# cloudArray2.net
KiCad netlist of a schematic drawn in EAGLE
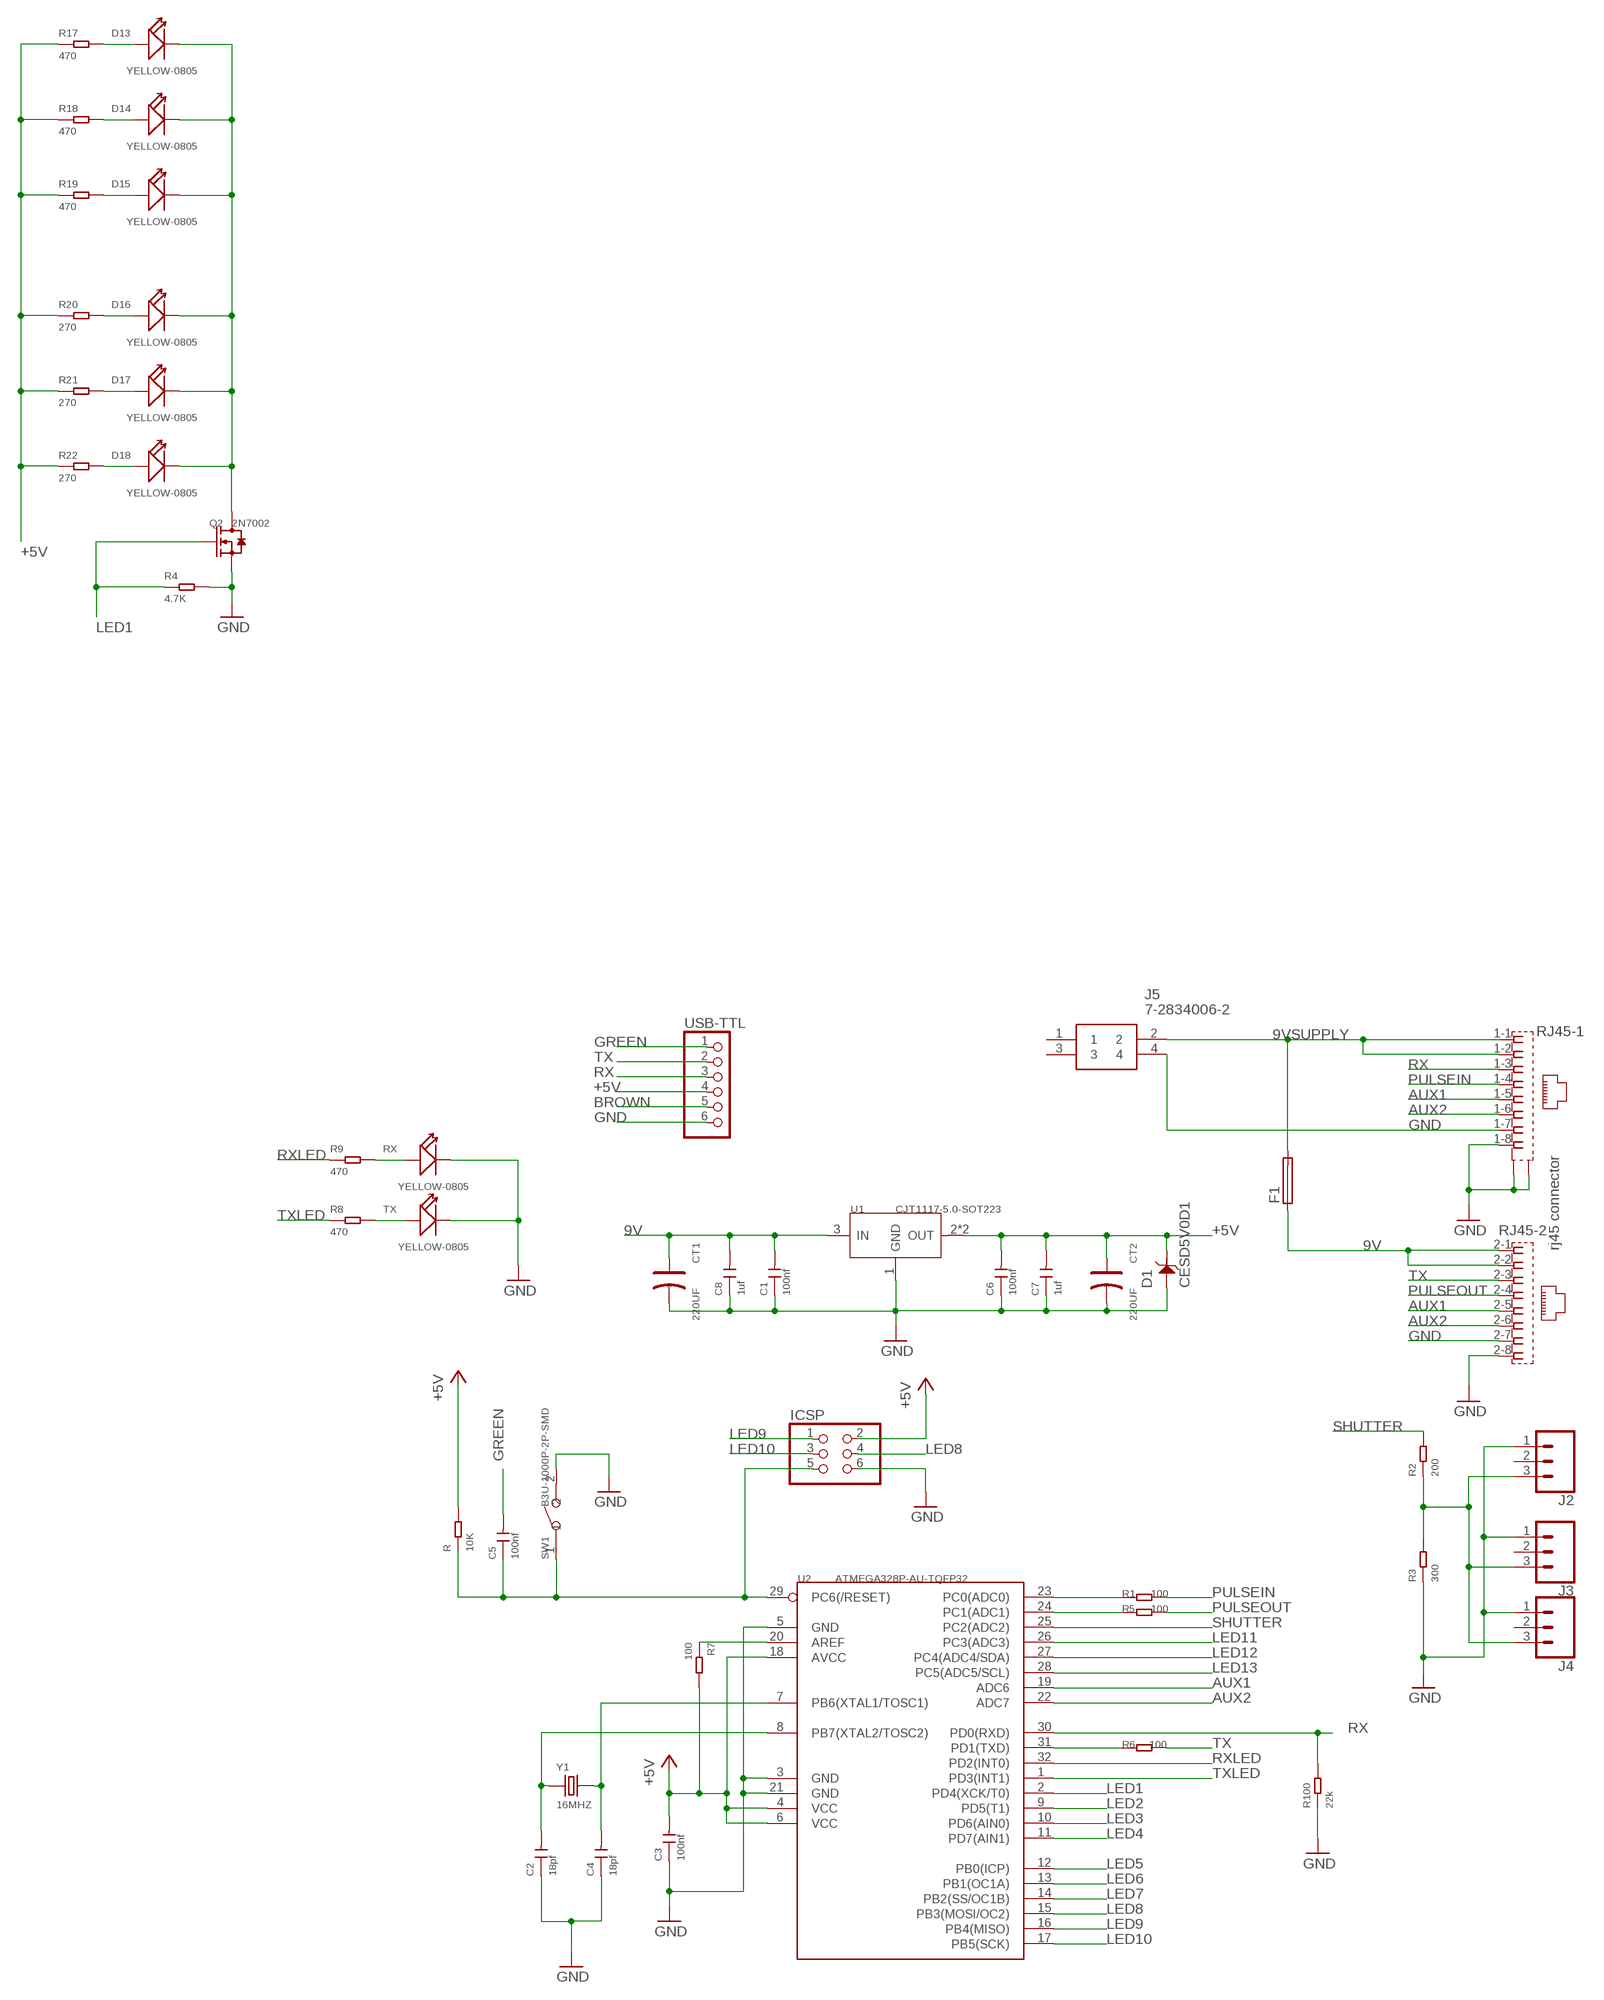
[diagram p0: schematic, sheet 1]
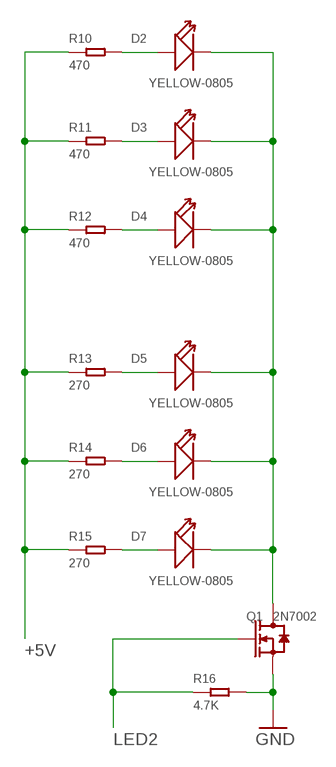
[diagram p1: schematic, sheet 2]
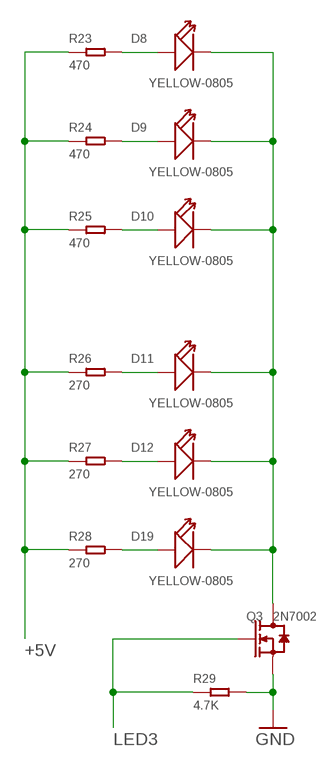
[diagram p2: schematic, sheet 3]
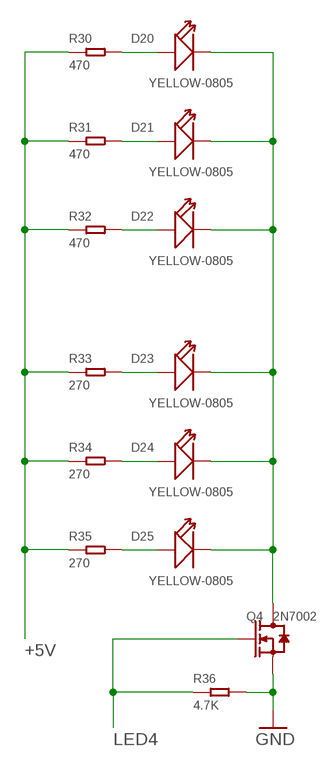
[diagram p3: schematic, sheet 4]
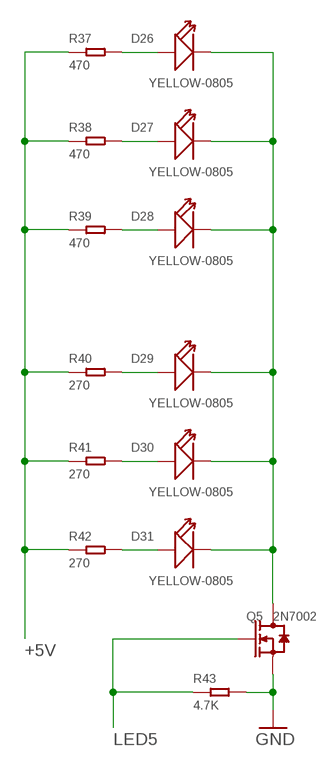
[diagram p4: schematic, sheet 5]
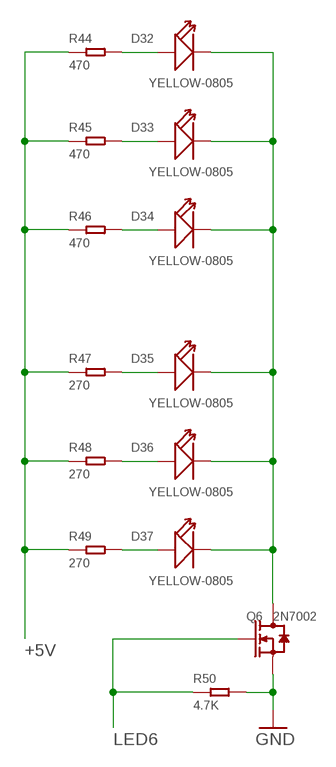
[diagram p5: schematic, sheet 6]
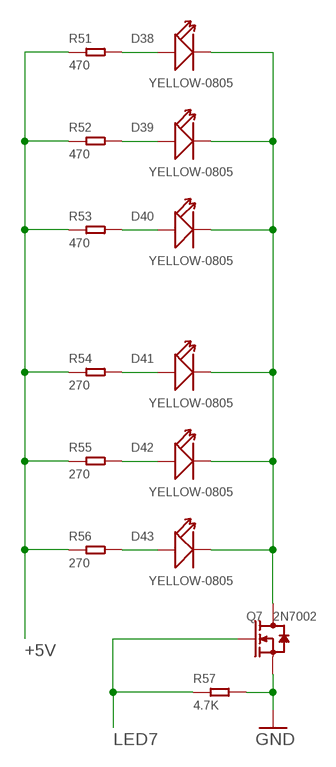
[diagram p6: schematic, sheet 7]
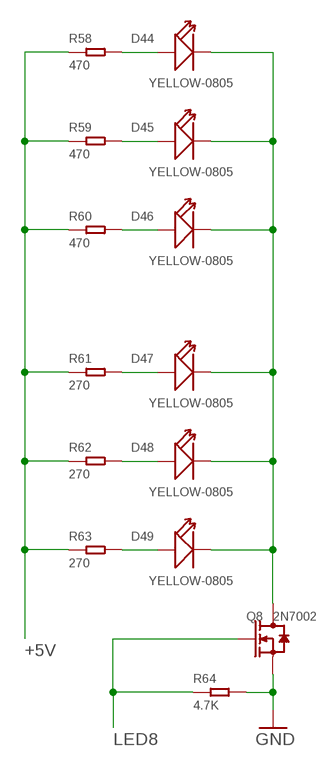
[diagram p7: schematic, sheet 8]
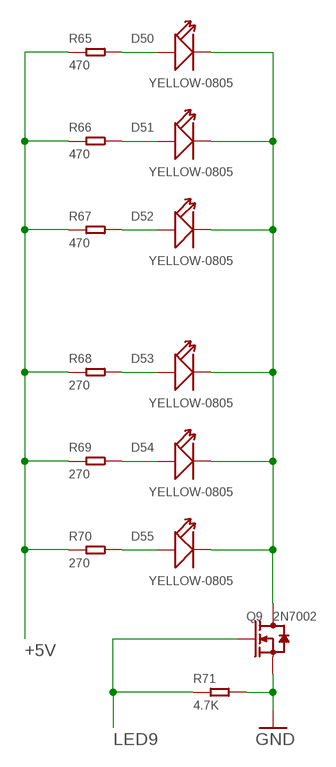
[diagram p8: schematic, sheet 9]
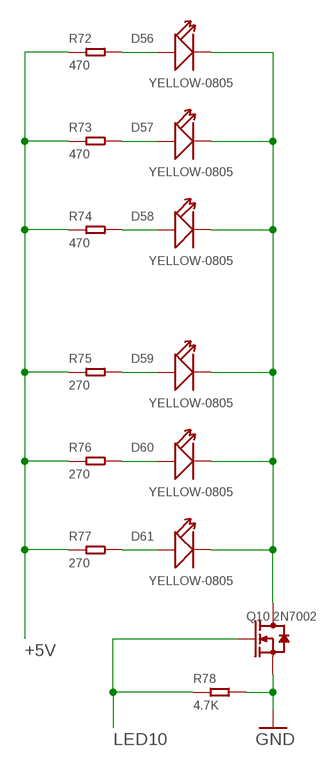
[diagram p9: schematic, sheet 10]
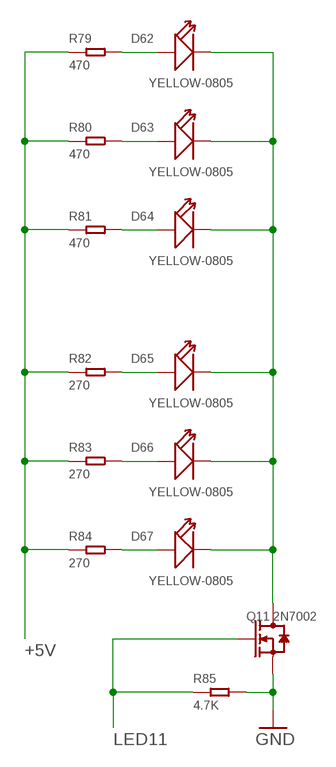
[diagram p10: schematic, sheet 11]
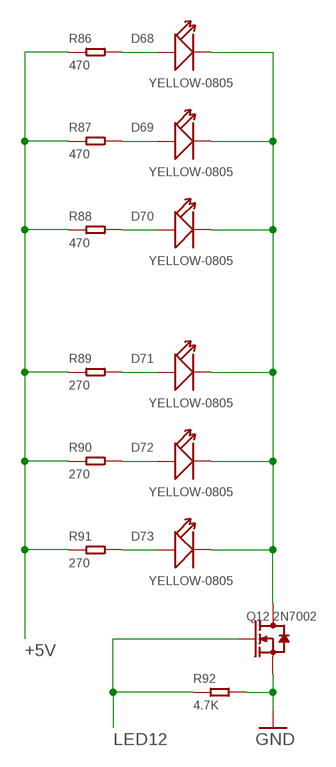
[diagram p11: schematic, sheet 12]
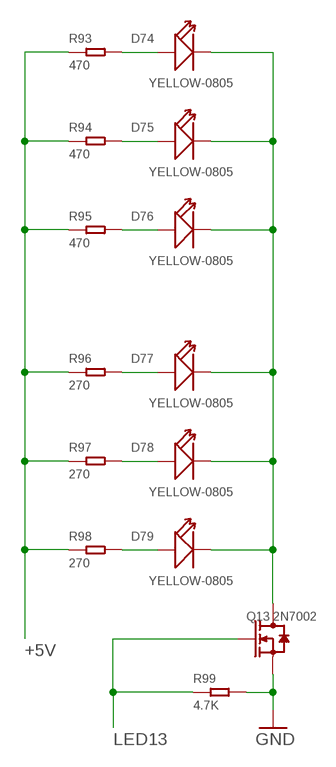
[diagram p12: schematic, sheet 13]

(export (version "E")
  (design (tool "Eeschema 10.0.6"))
  (components
    (comp (ref "D38")
      (value "YELLOW-0805")
      (footprint "eagle-import:LED-0805")
      (fields (field (name "MPN") "17-215UYC/S530-A3/TR8"))
      (libsource (lib "eagle-import") (part "SMD-LED-CLEAR-YELLOW(0805)"))
    )
    (comp (ref "D39")
      (value "YELLOW-0805")
      (footprint "eagle-import:LED-0805")
      (fields (field (name "MPN") "17-215UYC/S530-A3/TR8"))
      (libsource (lib "eagle-import") (part "SMD-LED-CLEAR-YELLOW(0805)"))
    )
    (comp (ref "D40")
      (value "YELLOW-0805")
      (footprint "eagle-import:LED-0805")
      (fields (field (name "MPN") "17-215UYC/S530-A3/TR8"))
      (libsource (lib "eagle-import") (part "SMD-LED-CLEAR-YELLOW(0805)"))
    )
    (comp (ref "D41")
      (value "YELLOW-0805")
      (footprint "eagle-import:LED-0805")
      (fields (field (name "MPN") "17-215UYC/S530-A3/TR8"))
      (libsource (lib "eagle-import") (part "SMD-LED-CLEAR-YELLOW(0805)"))
    )
    (comp (ref "D42")
      (value "YELLOW-0805")
      (footprint "eagle-import:LED-0805")
      (fields (field (name "MPN") "17-215UYC/S530-A3/TR8"))
      (libsource (lib "eagle-import") (part "SMD-LED-CLEAR-YELLOW(0805)"))
    )
    (comp (ref "D43")
      (value "YELLOW-0805")
      (footprint "eagle-import:LED-0805")
      (fields (field (name "MPN") "17-215UYC/S530-A3/TR8"))
      (libsource (lib "eagle-import") (part "SMD-LED-CLEAR-YELLOW(0805)"))
    )
    (comp (ref "Q7")
      (value "2N7002")
      (footprint "eagle-import:SOT-23")
      (fields (field (name "MPN") "2N7002,215"))
      (libsource (lib "eagle-import") (part "SMD-MOSFET-N-CH-60V-300MA-LOGIC-LEVEL-FET-2N7002(SOT-23)"))
    )
    (comp (ref "R51")
      (value "470")
      (footprint "eagle-import:R0805")
      (fields (field (name "MPN") "RC0805JR-071KL"))
      (libsource (lib "eagle-import") (part "SMD-RES-470R-1%-1/8W(0805)"))
    )
    (comp (ref "R52")
      (value "470")
      (footprint "eagle-import:R0805")
      (fields (field (name "MPN") "RC0805JR-071KL"))
      (libsource (lib "eagle-import") (part "SMD-RES-470R-1%-1/8W(0805)"))
    )
    (comp (ref "R53")
      (value "470")
      (footprint "eagle-import:R0805")
      (fields (field (name "MPN") "RC0805JR-071KL"))
      (libsource (lib "eagle-import") (part "SMD-RES-470R-1%-1/8W(0805)"))
    )
    (comp (ref "R54")
      (value "270")
      (footprint "eagle-import:R0805")
      (fields (field (name "MPN") "RC0805JR-071KL"))
      (libsource (lib "eagle-import") (part "SMD-RES-470R-1%-1/8W(0805)"))
    )
    (comp (ref "R55")
      (value "270")
      (footprint "eagle-import:R0805")
      (fields (field (name "MPN") "RC0805JR-071KL"))
      (libsource (lib "eagle-import") (part "SMD-RES-470R-1%-1/8W(0805)"))
    )
    (comp (ref "R56")
      (value "270")
      (footprint "eagle-import:R0805")
      (fields (field (name "MPN") "RC0805JR-071KL"))
      (libsource (lib "eagle-import") (part "SMD-RES-470R-1%-1/8W(0805)"))
    )
    (comp (ref "R57")
      (value "4.7K")
      (footprint "eagle-import:R0805")
      (fields (field (name "MPN") "RC0805JR-071KL"))
      (libsource (lib "eagle-import") (part "SMD-RES-2.4K-5%-1/8W(0805)"))
    )
    (comp (ref "D50")
      (value "YELLOW-0805")
      (footprint "eagle-import:LED-0805")
      (fields (field (name "MPN") "17-215UYC/S530-A3/TR8"))
      (libsource (lib "eagle-import") (part "SMD-LED-CLEAR-YELLOW(0805)"))
    )
    (comp (ref "D51")
      (value "YELLOW-0805")
      (footprint "eagle-import:LED-0805")
      (fields (field (name "MPN") "17-215UYC/S530-A3/TR8"))
      (libsource (lib "eagle-import") (part "SMD-LED-CLEAR-YELLOW(0805)"))
    )
    (comp (ref "D52")
      (value "YELLOW-0805")
      (footprint "eagle-import:LED-0805")
      (fields (field (name "MPN") "17-215UYC/S530-A3/TR8"))
      (libsource (lib "eagle-import") (part "SMD-LED-CLEAR-YELLOW(0805)"))
    )
    (comp (ref "D53")
      (value "YELLOW-0805")
      (footprint "eagle-import:LED-0805")
      (fields (field (name "MPN") "17-215UYC/S530-A3/TR8"))
      (libsource (lib "eagle-import") (part "SMD-LED-CLEAR-YELLOW(0805)"))
    )
    (comp (ref "D54")
      (value "YELLOW-0805")
      (footprint "eagle-import:LED-0805")
      (fields (field (name "MPN") "17-215UYC/S530-A3/TR8"))
      (libsource (lib "eagle-import") (part "SMD-LED-CLEAR-YELLOW(0805)"))
    )
    (comp (ref "D55")
      (value "YELLOW-0805")
      (footprint "eagle-import:LED-0805")
      (fields (field (name "MPN") "17-215UYC/S530-A3/TR8"))
      (libsource (lib "eagle-import") (part "SMD-LED-CLEAR-YELLOW(0805)"))
    )
    (comp (ref "Q9")
      (value "2N7002")
      (footprint "eagle-import:SOT-23")
      (fields (field (name "MPN") "2N7002,215"))
      (libsource (lib "eagle-import") (part "SMD-MOSFET-N-CH-60V-300MA-LOGIC-LEVEL-FET-2N7002(SOT-23)"))
    )
    (comp (ref "R65")
      (value "470")
      (footprint "eagle-import:R0805")
      (fields (field (name "MPN") "RC0805JR-071KL"))
      (libsource (lib "eagle-import") (part "SMD-RES-470R-1%-1/8W(0805)"))
    )
    (comp (ref "R66")
      (value "470")
      (footprint "eagle-import:R0805")
      (fields (field (name "MPN") "RC0805JR-071KL"))
      (libsource (lib "eagle-import") (part "SMD-RES-470R-1%-1/8W(0805)"))
    )
    (comp (ref "R67")
      (value "470")
      (footprint "eagle-import:R0805")
      (fields (field (name "MPN") "RC0805JR-071KL"))
      (libsource (lib "eagle-import") (part "SMD-RES-470R-1%-1/8W(0805)"))
    )
    (comp (ref "R68")
      (value "270")
      (footprint "eagle-import:R0805")
      (fields (field (name "MPN") "RC0805JR-071KL"))
      (libsource (lib "eagle-import") (part "SMD-RES-470R-1%-1/8W(0805)"))
    )
    (comp (ref "R69")
      (value "270")
      (footprint "eagle-import:R0805")
      (fields (field (name "MPN") "RC0805JR-071KL"))
      (libsource (lib "eagle-import") (part "SMD-RES-470R-1%-1/8W(0805)"))
    )
    (comp (ref "R70")
      (value "270")
      (footprint "eagle-import:R0805")
      (fields (field (name "MPN") "RC0805JR-071KL"))
      (libsource (lib "eagle-import") (part "SMD-RES-470R-1%-1/8W(0805)"))
    )
    (comp (ref "R71")
      (value "4.7K")
      (footprint "eagle-import:R0805")
      (fields (field (name "MPN") "RC0805JR-071KL"))
      (libsource (lib "eagle-import") (part "SMD-RES-2.4K-5%-1/8W(0805)"))
    )
    (comp (ref "D68")
      (value "YELLOW-0805")
      (footprint "eagle-import:LED-0805")
      (fields (field (name "MPN") "17-215UYC/S530-A3/TR8"))
      (libsource (lib "eagle-import") (part "SMD-LED-CLEAR-YELLOW(0805)"))
    )
    (comp (ref "D69")
      (value "YELLOW-0805")
      (footprint "eagle-import:LED-0805")
      (fields (field (name "MPN") "17-215UYC/S530-A3/TR8"))
      (libsource (lib "eagle-import") (part "SMD-LED-CLEAR-YELLOW(0805)"))
    )
    (comp (ref "D70")
      (value "YELLOW-0805")
      (footprint "eagle-import:LED-0805")
      (fields (field (name "MPN") "17-215UYC/S530-A3/TR8"))
      (libsource (lib "eagle-import") (part "SMD-LED-CLEAR-YELLOW(0805)"))
    )
    (comp (ref "D71")
      (value "YELLOW-0805")
      (footprint "eagle-import:LED-0805")
      (fields (field (name "MPN") "17-215UYC/S530-A3/TR8"))
      (libsource (lib "eagle-import") (part "SMD-LED-CLEAR-YELLOW(0805)"))
    )
    (comp (ref "D72")
      (value "YELLOW-0805")
      (footprint "eagle-import:LED-0805")
      (fields (field (name "MPN") "17-215UYC/S530-A3/TR8"))
      (libsource (lib "eagle-import") (part "SMD-LED-CLEAR-YELLOW(0805)"))
    )
    (comp (ref "D73")
      (value "YELLOW-0805")
      (footprint "eagle-import:LED-0805")
      (fields (field (name "MPN") "17-215UYC/S530-A3/TR8"))
      (libsource (lib "eagle-import") (part "SMD-LED-CLEAR-YELLOW(0805)"))
    )
    (comp (ref "Q12")
      (value "2N7002")
      (footprint "eagle-import:SOT-23")
      (fields (field (name "MPN") "2N7002,215"))
      (libsource (lib "eagle-import") (part "SMD-MOSFET-N-CH-60V-300MA-LOGIC-LEVEL-FET-2N7002(SOT-23)"))
    )
    (comp (ref "R86")
      (value "470")
      (footprint "eagle-import:R0805")
      (fields (field (name "MPN") "RC0805JR-071KL"))
      (libsource (lib "eagle-import") (part "SMD-RES-470R-1%-1/8W(0805)"))
    )
    (comp (ref "R87")
      (value "470")
      (footprint "eagle-import:R0805")
      (fields (field (name "MPN") "RC0805JR-071KL"))
      (libsource (lib "eagle-import") (part "SMD-RES-470R-1%-1/8W(0805)"))
    )
    (comp (ref "R88")
      (value "470")
      (footprint "eagle-import:R0805")
      (fields (field (name "MPN") "RC0805JR-071KL"))
      (libsource (lib "eagle-import") (part "SMD-RES-470R-1%-1/8W(0805)"))
    )
    (comp (ref "R89")
      (value "270")
      (footprint "eagle-import:R0805")
      (fields (field (name "MPN") "RC0805JR-071KL"))
      (libsource (lib "eagle-import") (part "SMD-RES-470R-1%-1/8W(0805)"))
    )
    (comp (ref "R90")
      (value "270")
      (footprint "eagle-import:R0805")
      (fields (field (name "MPN") "RC0805JR-071KL"))
      (libsource (lib "eagle-import") (part "SMD-RES-470R-1%-1/8W(0805)"))
    )
    (comp (ref "R91")
      (value "270")
      (footprint "eagle-import:R0805")
      (fields (field (name "MPN") "RC0805JR-071KL"))
      (libsource (lib "eagle-import") (part "SMD-RES-470R-1%-1/8W(0805)"))
    )
    (comp (ref "R92")
      (value "4.7K")
      (footprint "eagle-import:R0805")
      (fields (field (name "MPN") "RC0805JR-071KL"))
      (libsource (lib "eagle-import") (part "SMD-RES-2.4K-5%-1/8W(0805)"))
    )
    (comp (ref "D26")
      (value "YELLOW-0805")
      (footprint "eagle-import:LED-0805")
      (fields (field (name "MPN") "17-215UYC/S530-A3/TR8"))
      (libsource (lib "eagle-import") (part "SMD-LED-CLEAR-YELLOW(0805)"))
    )
    (comp (ref "D27")
      (value "YELLOW-0805")
      (footprint "eagle-import:LED-0805")
      (fields (field (name "MPN") "17-215UYC/S530-A3/TR8"))
      (libsource (lib "eagle-import") (part "SMD-LED-CLEAR-YELLOW(0805)"))
    )
    (comp (ref "D28")
      (value "YELLOW-0805")
      (footprint "eagle-import:LED-0805")
      (fields (field (name "MPN") "17-215UYC/S530-A3/TR8"))
      (libsource (lib "eagle-import") (part "SMD-LED-CLEAR-YELLOW(0805)"))
    )
    (comp (ref "D29")
      (value "YELLOW-0805")
      (footprint "eagle-import:LED-0805")
      (fields (field (name "MPN") "17-215UYC/S530-A3/TR8"))
      (libsource (lib "eagle-import") (part "SMD-LED-CLEAR-YELLOW(0805)"))
    )
    (comp (ref "D30")
      (value "YELLOW-0805")
      (footprint "eagle-import:LED-0805")
      (fields (field (name "MPN") "17-215UYC/S530-A3/TR8"))
      (libsource (lib "eagle-import") (part "SMD-LED-CLEAR-YELLOW(0805)"))
    )
    (comp (ref "D31")
      (value "YELLOW-0805")
      (footprint "eagle-import:LED-0805")
      (fields (field (name "MPN") "17-215UYC/S530-A3/TR8"))
      (libsource (lib "eagle-import") (part "SMD-LED-CLEAR-YELLOW(0805)"))
    )
    (comp (ref "Q5")
      (value "2N7002")
      (footprint "eagle-import:SOT-23")
      (fields (field (name "MPN") "2N7002,215"))
      (libsource (lib "eagle-import") (part "SMD-MOSFET-N-CH-60V-300MA-LOGIC-LEVEL-FET-2N7002(SOT-23)"))
    )
    (comp (ref "R37")
      (value "470")
      (footprint "eagle-import:R0805")
      (fields (field (name "MPN") "RC0805JR-071KL"))
      (libsource (lib "eagle-import") (part "SMD-RES-470R-1%-1/8W(0805)"))
    )
    (comp (ref "R38")
      (value "470")
      (footprint "eagle-import:R0805")
      (fields (field (name "MPN") "RC0805JR-071KL"))
      (libsource (lib "eagle-import") (part "SMD-RES-470R-1%-1/8W(0805)"))
    )
    (comp (ref "R39")
      (value "470")
      (footprint "eagle-import:R0805")
      (fields (field (name "MPN") "RC0805JR-071KL"))
      (libsource (lib "eagle-import") (part "SMD-RES-470R-1%-1/8W(0805)"))
    )
    (comp (ref "R40")
      (value "270")
      (footprint "eagle-import:R0805")
      (fields (field (name "MPN") "RC0805JR-071KL"))
      (libsource (lib "eagle-import") (part "SMD-RES-470R-1%-1/8W(0805)"))
    )
    (comp (ref "R41")
      (value "270")
      (footprint "eagle-import:R0805")
      (fields (field (name "MPN") "RC0805JR-071KL"))
      (libsource (lib "eagle-import") (part "SMD-RES-470R-1%-1/8W(0805)"))
    )
    (comp (ref "R42")
      (value "270")
      (footprint "eagle-import:R0805")
      (fields (field (name "MPN") "RC0805JR-071KL"))
      (libsource (lib "eagle-import") (part "SMD-RES-470R-1%-1/8W(0805)"))
    )
    (comp (ref "R43")
      (value "4.7K")
      (footprint "eagle-import:R0805")
      (fields (field (name "MPN") "RC0805JR-071KL"))
      (libsource (lib "eagle-import") (part "SMD-RES-2.4K-5%-1/8W(0805)"))
    )
    (comp (ref "D74")
      (value "YELLOW-0805")
      (footprint "eagle-import:LED-0805")
      (fields (field (name "MPN") "17-215UYC/S530-A3/TR8"))
      (libsource (lib "eagle-import") (part "SMD-LED-CLEAR-YELLOW(0805)"))
    )
    (comp (ref "D75")
      (value "YELLOW-0805")
      (footprint "eagle-import:LED-0805")
      (fields (field (name "MPN") "17-215UYC/S530-A3/TR8"))
      (libsource (lib "eagle-import") (part "SMD-LED-CLEAR-YELLOW(0805)"))
    )
    (comp (ref "D76")
      (value "YELLOW-0805")
      (footprint "eagle-import:LED-0805")
      (fields (field (name "MPN") "17-215UYC/S530-A3/TR8"))
      (libsource (lib "eagle-import") (part "SMD-LED-CLEAR-YELLOW(0805)"))
    )
    (comp (ref "D77")
      (value "YELLOW-0805")
      (footprint "eagle-import:LED-0805")
      (fields (field (name "MPN") "17-215UYC/S530-A3/TR8"))
      (libsource (lib "eagle-import") (part "SMD-LED-CLEAR-YELLOW(0805)"))
    )
    (comp (ref "D78")
      (value "YELLOW-0805")
      (footprint "eagle-import:LED-0805")
      (fields (field (name "MPN") "17-215UYC/S530-A3/TR8"))
      (libsource (lib "eagle-import") (part "SMD-LED-CLEAR-YELLOW(0805)"))
    )
    (comp (ref "D79")
      (value "YELLOW-0805")
      (footprint "eagle-import:LED-0805")
      (fields (field (name "MPN") "17-215UYC/S530-A3/TR8"))
      (libsource (lib "eagle-import") (part "SMD-LED-CLEAR-YELLOW(0805)"))
    )
    (comp (ref "Q13")
      (value "2N7002")
      (footprint "eagle-import:SOT-23")
      (fields (field (name "MPN") "2N7002,215"))
      (libsource (lib "eagle-import") (part "SMD-MOSFET-N-CH-60V-300MA-LOGIC-LEVEL-FET-2N7002(SOT-23)"))
    )
    (comp (ref "R93")
      (value "470")
      (footprint "eagle-import:R0805")
      (fields (field (name "MPN") "RC0805JR-071KL"))
      (libsource (lib "eagle-import") (part "SMD-RES-470R-1%-1/8W(0805)"))
    )
    (comp (ref "R94")
      (value "470")
      (footprint "eagle-import:R0805")
      (fields (field (name "MPN") "RC0805JR-071KL"))
      (libsource (lib "eagle-import") (part "SMD-RES-470R-1%-1/8W(0805)"))
    )
    (comp (ref "R95")
      (value "470")
      (footprint "eagle-import:R0805")
      (fields (field (name "MPN") "RC0805JR-071KL"))
      (libsource (lib "eagle-import") (part "SMD-RES-470R-1%-1/8W(0805)"))
    )
    (comp (ref "R96")
      (value "270")
      (footprint "eagle-import:R0805")
      (fields (field (name "MPN") "RC0805JR-071KL"))
      (libsource (lib "eagle-import") (part "SMD-RES-470R-1%-1/8W(0805)"))
    )
    (comp (ref "R97")
      (value "270")
      (footprint "eagle-import:R0805")
      (fields (field (name "MPN") "RC0805JR-071KL"))
      (libsource (lib "eagle-import") (part "SMD-RES-470R-1%-1/8W(0805)"))
    )
    (comp (ref "R98")
      (value "270")
      (footprint "eagle-import:R0805")
      (fields (field (name "MPN") "RC0805JR-071KL"))
      (libsource (lib "eagle-import") (part "SMD-RES-470R-1%-1/8W(0805)"))
    )
    (comp (ref "R99")
      (value "4.7K")
      (footprint "eagle-import:R0805")
      (fields (field (name "MPN") "RC0805JR-071KL"))
      (libsource (lib "eagle-import") (part "SMD-RES-2.4K-5%-1/8W(0805)"))
    )
    (comp (ref "D20")
      (value "YELLOW-0805")
      (footprint "eagle-import:LED-0805")
      (fields (field (name "MPN") "17-215UYC/S530-A3/TR8"))
      (libsource (lib "eagle-import") (part "SMD-LED-CLEAR-YELLOW(0805)"))
    )
    (comp (ref "D21")
      (value "YELLOW-0805")
      (footprint "eagle-import:LED-0805")
      (fields (field (name "MPN") "17-215UYC/S530-A3/TR8"))
      (libsource (lib "eagle-import") (part "SMD-LED-CLEAR-YELLOW(0805)"))
    )
    (comp (ref "D22")
      (value "YELLOW-0805")
      (footprint "eagle-import:LED-0805")
      (fields (field (name "MPN") "17-215UYC/S530-A3/TR8"))
      (libsource (lib "eagle-import") (part "SMD-LED-CLEAR-YELLOW(0805)"))
    )
    (comp (ref "D23")
      (value "YELLOW-0805")
      (footprint "eagle-import:LED-0805")
      (fields (field (name "MPN") "17-215UYC/S530-A3/TR8"))
      (libsource (lib "eagle-import") (part "SMD-LED-CLEAR-YELLOW(0805)"))
    )
    (comp (ref "D24")
      (value "YELLOW-0805")
      (footprint "eagle-import:LED-0805")
      (fields (field (name "MPN") "17-215UYC/S530-A3/TR8"))
      (libsource (lib "eagle-import") (part "SMD-LED-CLEAR-YELLOW(0805)"))
    )
    (comp (ref "D25")
      (value "YELLOW-0805")
      (footprint "eagle-import:LED-0805")
      (fields (field (name "MPN") "17-215UYC/S530-A3/TR8"))
      (libsource (lib "eagle-import") (part "SMD-LED-CLEAR-YELLOW(0805)"))
    )
    (comp (ref "Q4")
      (value "2N7002")
      (footprint "eagle-import:SOT-23")
      (fields (field (name "MPN") "2N7002,215"))
      (libsource (lib "eagle-import") (part "SMD-MOSFET-N-CH-60V-300MA-LOGIC-LEVEL-FET-2N7002(SOT-23)"))
    )
    (comp (ref "R30")
      (value "470")
      (footprint "eagle-import:R0805")
      (fields (field (name "MPN") "RC0805JR-071KL"))
      (libsource (lib "eagle-import") (part "SMD-RES-470R-1%-1/8W(0805)"))
    )
    (comp (ref "R31")
      (value "470")
      (footprint "eagle-import:R0805")
      (fields (field (name "MPN") "RC0805JR-071KL"))
      (libsource (lib "eagle-import") (part "SMD-RES-470R-1%-1/8W(0805)"))
    )
    (comp (ref "R32")
      (value "470")
      (footprint "eagle-import:R0805")
      (fields (field (name "MPN") "RC0805JR-071KL"))
      (libsource (lib "eagle-import") (part "SMD-RES-470R-1%-1/8W(0805)"))
    )
    (comp (ref "R33")
      (value "270")
      (footprint "eagle-import:R0805")
      (fields (field (name "MPN") "RC0805JR-071KL"))
      (libsource (lib "eagle-import") (part "SMD-RES-470R-1%-1/8W(0805)"))
    )
    (comp (ref "R34")
      (value "270")
      (footprint "eagle-import:R0805")
      (fields (field (name "MPN") "RC0805JR-071KL"))
      (libsource (lib "eagle-import") (part "SMD-RES-470R-1%-1/8W(0805)"))
    )
    (comp (ref "R35")
      (value "270")
      (footprint "eagle-import:R0805")
      (fields (field (name "MPN") "RC0805JR-071KL"))
      (libsource (lib "eagle-import") (part "SMD-RES-470R-1%-1/8W(0805)"))
    )
    (comp (ref "R36")
      (value "4.7K")
      (footprint "eagle-import:R0805")
      (fields (field (name "MPN") "RC0805JR-071KL"))
      (libsource (lib "eagle-import") (part "SMD-RES-2.4K-5%-1/8W(0805)"))
    )
    (comp (ref "D44")
      (value "YELLOW-0805")
      (footprint "eagle-import:LED-0805")
      (fields (field (name "MPN") "17-215UYC/S530-A3/TR8"))
      (libsource (lib "eagle-import") (part "SMD-LED-CLEAR-YELLOW(0805)"))
    )
    (comp (ref "D45")
      (value "YELLOW-0805")
      (footprint "eagle-import:LED-0805")
      (fields (field (name "MPN") "17-215UYC/S530-A3/TR8"))
      (libsource (lib "eagle-import") (part "SMD-LED-CLEAR-YELLOW(0805)"))
    )
    (comp (ref "D46")
      (value "YELLOW-0805")
      (footprint "eagle-import:LED-0805")
      (fields (field (name "MPN") "17-215UYC/S530-A3/TR8"))
      (libsource (lib "eagle-import") (part "SMD-LED-CLEAR-YELLOW(0805)"))
    )
    (comp (ref "D47")
      (value "YELLOW-0805")
      (footprint "eagle-import:LED-0805")
      (fields (field (name "MPN") "17-215UYC/S530-A3/TR8"))
      (libsource (lib "eagle-import") (part "SMD-LED-CLEAR-YELLOW(0805)"))
    )
    (comp (ref "D48")
      (value "YELLOW-0805")
      (footprint "eagle-import:LED-0805")
      (fields (field (name "MPN") "17-215UYC/S530-A3/TR8"))
      (libsource (lib "eagle-import") (part "SMD-LED-CLEAR-YELLOW(0805)"))
    )
    (comp (ref "D49")
      (value "YELLOW-0805")
      (footprint "eagle-import:LED-0805")
      (fields (field (name "MPN") "17-215UYC/S530-A3/TR8"))
      (libsource (lib "eagle-import") (part "SMD-LED-CLEAR-YELLOW(0805)"))
    )
    (comp (ref "Q8")
      (value "2N7002")
      (footprint "eagle-import:SOT-23")
      (fields (field (name "MPN") "2N7002,215"))
      (libsource (lib "eagle-import") (part "SMD-MOSFET-N-CH-60V-300MA-LOGIC-LEVEL-FET-2N7002(SOT-23)"))
    )
    (comp (ref "R58")
      (value "470")
      (footprint "eagle-import:R0805")
      (fields (field (name "MPN") "RC0805JR-071KL"))
      (libsource (lib "eagle-import") (part "SMD-RES-470R-1%-1/8W(0805)"))
    )
    (comp (ref "R59")
      (value "470")
      (footprint "eagle-import:R0805")
      (fields (field (name "MPN") "RC0805JR-071KL"))
      (libsource (lib "eagle-import") (part "SMD-RES-470R-1%-1/8W(0805)"))
    )
    (comp (ref "R60")
      (value "470")
      (footprint "eagle-import:R0805")
      (fields (field (name "MPN") "RC0805JR-071KL"))
      (libsource (lib "eagle-import") (part "SMD-RES-470R-1%-1/8W(0805)"))
    )
    (comp (ref "R61")
      (value "270")
      (footprint "eagle-import:R0805")
      (fields (field (name "MPN") "RC0805JR-071KL"))
      (libsource (lib "eagle-import") (part "SMD-RES-470R-1%-1/8W(0805)"))
    )
    (comp (ref "R62")
      (value "270")
      (footprint "eagle-import:R0805")
      (fields (field (name "MPN") "RC0805JR-071KL"))
      (libsource (lib "eagle-import") (part "SMD-RES-470R-1%-1/8W(0805)"))
    )
    (comp (ref "R63")
      (value "270")
      (footprint "eagle-import:R0805")
      (fields (field (name "MPN") "RC0805JR-071KL"))
      (libsource (lib "eagle-import") (part "SMD-RES-470R-1%-1/8W(0805)"))
    )
    (comp (ref "R64")
      (value "4.7K")
      (footprint "eagle-import:R0805")
      (fields (field (name "MPN") "RC0805JR-071KL"))
      (libsource (lib "eagle-import") (part "SMD-RES-2.4K-5%-1/8W(0805)"))
    )
    (comp (ref "C1")
      (value "100nf")
      (footprint "eagle-import:C0805")
      (fields (field (name "MPN") "CC0805KRX7R9BB104"))
      (libsource (lib "eagle-import") (part "CERAMIC-100NF-50V-10%-X7R(0805)"))
    )
    (comp (ref "C2")
      (value "18pf")
      (footprint "eagle-import:C0805")
      (fields (field (name "MPN") "CC0805KKX7R8BB105"))
      (libsource (lib "eagle-import") (part "CERAMIC-1UF-25V-10%-X7R(0805)"))
    )
    (comp (ref "C3")
      (value "100nf")
      (footprint "eagle-import:C0805")
      (fields (field (name "MPN") "CC0805JRX7R9BB103"))
      (libsource (lib "eagle-import") (part "CERAMIC-10NF-50V-5%-X7R(0805)"))
    )
    (comp (ref "C4")
      (value "18pf")
      (footprint "eagle-import:C0805")
      (fields (field (name "MPN") "CC0805KKX7R8BB105"))
      (libsource (lib "eagle-import") (part "CERAMIC-1UF-25V-10%-X7R(0805)"))
    )
    (comp (ref "C5")
      (value "100nf")
      (footprint "eagle-import:C0805")
      (fields (field (name "MPN") "CC0805KRX7R9BB104"))
      (libsource (lib "eagle-import") (part "CERAMIC-100NF-50V-10%-X7R(0805)"))
    )
    (comp (ref "C6")
      (value "100nf")
      (footprint "eagle-import:C0805")
      (fields (field (name "MPN") "CC0805KRX7R9BB104"))
      (libsource (lib "eagle-import") (part "CERAMIC-100NF-50V-10%-X7R(0805)"))
    )
    (comp (ref "C7")
      (value "1uf")
      (footprint "eagle-import:C0805")
      (fields (field (name "MPN") "CC0805KRX7R9BB104"))
      (libsource (lib "eagle-import") (part "CERAMIC-100NF-50V-10%-X7R(0805)"))
    )
    (comp (ref "C8")
      (value "1uf")
      (footprint "eagle-import:C0805")
      (fields (field (name "MPN") "CC0805KRX7R9BB104"))
      (libsource (lib "eagle-import") (part "CERAMIC-100NF-50V-10%-X7R(0805)"))
    )
    (comp (ref "CT1")
      (value "220UF")
      (footprint "eagle-import:ELECTRO-SMD-C-6MM")
      (fields (field (name "MPN") "CS1E221M-CRE77"))
      (libsource (lib "eagle-import") (part "ALUMINUM-SMD-220UF-16V(D6.3-H7.7MM)"))
    )
    (comp (ref "CT2")
      (value "220UF")
      (footprint "eagle-import:ELECTRO-SMD-C-6MM")
      (fields (field (name "MPN") "CS1E221M-CRE77"))
      (libsource (lib "eagle-import") (part "ALUMINUM-SMD-220UF-16V(D6.3-H7.7MM)"))
    )
    (comp (ref "D1")
      (value "CESD5V0D1")
      (footprint "eagle-import:SOD-123")
      (libsource (lib "eagle-import") (part "SMD-DIODE-ESD-6.2V-250MW(SOD-123)"))
    )
    (comp (ref "D13")
      (value "YELLOW-0805")
      (footprint "eagle-import:LED-0805")
      (fields (field (name "MPN") "17-215UYC/S530-A3/TR8"))
      (libsource (lib "eagle-import") (part "SMD-LED-CLEAR-YELLOW(0805)"))
    )
    (comp (ref "D14")
      (value "YELLOW-0805")
      (footprint "eagle-import:LED-0805")
      (fields (field (name "MPN") "17-215UYC/S530-A3/TR8"))
      (libsource (lib "eagle-import") (part "SMD-LED-CLEAR-YELLOW(0805)"))
    )
    (comp (ref "D15")
      (value "YELLOW-0805")
      (footprint "eagle-import:LED-0805")
      (fields (field (name "MPN") "17-215UYC/S530-A3/TR8"))
      (libsource (lib "eagle-import") (part "SMD-LED-CLEAR-YELLOW(0805)"))
    )
    (comp (ref "D16")
      (value "YELLOW-0805")
      (footprint "eagle-import:LED-0805")
      (fields (field (name "MPN") "17-215UYC/S530-A3/TR8"))
      (libsource (lib "eagle-import") (part "SMD-LED-CLEAR-YELLOW(0805)"))
    )
    (comp (ref "D17")
      (value "YELLOW-0805")
      (footprint "eagle-import:LED-0805")
      (fields (field (name "MPN") "17-215UYC/S530-A3/TR8"))
      (libsource (lib "eagle-import") (part "SMD-LED-CLEAR-YELLOW(0805)"))
    )
    (comp (ref "D18")
      (value "YELLOW-0805")
      (footprint "eagle-import:LED-0805")
      (fields (field (name "MPN") "17-215UYC/S530-A3/TR8"))
      (libsource (lib "eagle-import") (part "SMD-LED-CLEAR-YELLOW(0805)"))
    )
    (comp (ref "F1")
      (value "SH22,5A")
      (footprint "eagle-import:SH22,5A")
      (fields (field (name "MPN") "0031.7701.11"))
      (libsource (lib "eagle-import") (part "SH22,5A"))
    )
    (comp (ref "ICSP")
      (value "PINHD-2X3")
      (footprint "eagle-import:2X03")
      (libsource (lib "eagle-import") (part "PINHD-2X3"))
    )
    (comp (ref "J2")
      (value "455-1750-1-ND")
      (footprint "eagle-import:1X03")
      (libsource (lib "eagle-import") (part "CONN_03"))
    )
    (comp (ref "J3")
      (value "455-1750-1-ND")
      (footprint "eagle-import:1X03")
      (libsource (lib "eagle-import") (part "CONN_03"))
    )
    (comp (ref "J4")
      (value "455-1750-1-ND")
      (footprint "eagle-import:1X03")
      (libsource (lib "eagle-import") (part "CONN_03"))
    )
    (comp (ref "J5")
      (value "7-2834006-2")
      (footprint "eagle-import:728340062")
      (fields (field (name "MOUSER_PART_NUMBER") "571-7-2834006-2"))
      (libsource (lib "eagle-import") (part "7-2834006-2"))
    )
    (comp (ref "Q2")
      (value "2N7002")
      (footprint "eagle-import:SOT-23")
      (fields (field (name "MPN") "2N7002,215"))
      (libsource (lib "eagle-import") (part "SMD-MOSFET-N-CH-60V-300MA-LOGIC-LEVEL-FET-2N7002(SOT-23)"))
    )
    (comp (ref "R")
      (value "10K")
      (footprint "eagle-import:R0805")
      (fields (field (name "MPN") "RC0805FR-0710KL"))
      (libsource (lib "eagle-import") (part "SMD-RES-10K-1%-1/8W(0805)"))
    )
    (comp (ref "R1")
      (value "100")
      (footprint "eagle-import:R0805")
      (fields (field (name "MPN") "RC0805JR-071KL"))
      (libsource (lib "eagle-import") (part "SMD-RES-200R-1%-1/8W(0805)"))
    )
    (comp (ref "R2")
      (value "200")
      (footprint "eagle-import:R0805")
      (fields (field (name "MPN") "RC0805JR-071KL"))
      (libsource (lib "eagle-import") (part "SMD-RES-200R-1%-1/8W(0805)"))
    )
    (comp (ref "R3")
      (value "300")
      (footprint "eagle-import:R0805")
      (fields (field (name "MPN") "RC0805JR-071KL"))
      (libsource (lib "eagle-import") (part "SMD-RES-200R-1%-1/8W(0805)"))
    )
    (comp (ref "R4")
      (value "4.7K")
      (footprint "eagle-import:R0805")
      (fields (field (name "MPN") "RC0805JR-071KL"))
      (libsource (lib "eagle-import") (part "SMD-RES-2.4K-5%-1/8W(0805)"))
    )
    (comp (ref "R5")
      (value "100")
      (footprint "eagle-import:R0805")
      (fields (field (name "MPN") "RC0805JR-071KL"))
      (libsource (lib "eagle-import") (part "SMD-RES-200R-1%-1/8W(0805)"))
    )
    (comp (ref "R6")
      (value "100")
      (footprint "eagle-import:R0805")
      (fields (field (name "MPN") "RC0805JR-071KL"))
      (libsource (lib "eagle-import") (part "SMD-RES-200R-1%-1/8W(0805)"))
    )
    (comp (ref "R7")
      (value "100")
      (footprint "eagle-import:R0805")
      (fields (field (name "MPN") "RC0805JR-071KL"))
      (libsource (lib "eagle-import") (part "SMD-RES-200R-1%-1/8W(0805)"))
    )
    (comp (ref "R8")
      (value "470")
      (footprint "eagle-import:R0805")
      (fields (field (name "MPN") "RC0805JR-071KL"))
      (libsource (lib "eagle-import") (part "SMD-RES-470R-1%-1/8W(0805)"))
    )
    (comp (ref "R9")
      (value "470")
      (footprint "eagle-import:R0805")
      (fields (field (name "MPN") "RC0805JR-071KL"))
      (libsource (lib "eagle-import") (part "SMD-RES-470R-1%-1/8W(0805)"))
    )
    (comp (ref "R17")
      (value "470")
      (footprint "eagle-import:R0805")
      (fields (field (name "MPN") "RC0805JR-071KL"))
      (libsource (lib "eagle-import") (part "SMD-RES-470R-1%-1/8W(0805)"))
    )
    (comp (ref "R18")
      (value "470")
      (footprint "eagle-import:R0805")
      (fields (field (name "MPN") "RC0805JR-071KL"))
      (libsource (lib "eagle-import") (part "SMD-RES-470R-1%-1/8W(0805)"))
    )
    (comp (ref "R19")
      (value "470")
      (footprint "eagle-import:R0805")
      (fields (field (name "MPN") "RC0805JR-071KL"))
      (libsource (lib "eagle-import") (part "SMD-RES-470R-1%-1/8W(0805)"))
    )
    (comp (ref "R20")
      (value "270")
      (footprint "eagle-import:R0805")
      (fields (field (name "MPN") "RC0805JR-071KL"))
      (libsource (lib "eagle-import") (part "SMD-RES-470R-1%-1/8W(0805)"))
    )
    (comp (ref "R21")
      (value "270")
      (footprint "eagle-import:R0805")
      (fields (field (name "MPN") "RC0805JR-071KL"))
      (libsource (lib "eagle-import") (part "SMD-RES-470R-1%-1/8W(0805)"))
    )
    (comp (ref "R22")
      (value "270")
      (footprint "eagle-import:R0805")
      (fields (field (name "MPN") "RC0805JR-071KL"))
      (libsource (lib "eagle-import") (part "SMD-RES-470R-1%-1/8W(0805)"))
    )
    (comp (ref "R100")
      (value "22k")
      (footprint "eagle-import:R0805")
      (fields (field (name "MPN") "RC0805JR-071KL"))
      (libsource (lib "eagle-import") (part "SMD-RES-200R-1%-1/8W(0805)"))
    )
    (comp (ref "RJ45")
      (value "557570-1")
      (footprint "eagle-import:557570-1")
      (libsource (lib "eagle-import") (part "557570-1"))
    )
    (comp (ref "RX")
      (value "YELLOW-0805")
      (footprint "eagle-import:LED-0805")
      (fields (field (name "MPN") "17-215UYC/S530-A3/TR8"))
      (libsource (lib "eagle-import") (part "SMD-LED-CLEAR-YELLOW(0805)"))
    )
    (comp (ref "SW1")
      (value "B3U-1000P-2P-SMD")
      (footprint "eagle-import:SW2-2.6-3.0X2.5X1.2+0.4MM")
      (libsource (lib "eagle-import") (part "SMD-BUTTON(2P-3.0X2.5X1.2+0.4MM)-B3U-1000P-2P-SMD"))
    )
    (comp (ref "TX")
      (value "YELLOW-0805")
      (footprint "eagle-import:LED-0805")
      (fields (field (name "MPN") "17-215UYC/S530-A3/TR8"))
      (libsource (lib "eagle-import") (part "SMD-LED-CLEAR-YELLOW(0805)"))
    )
    (comp (ref "U1")
      (value "CJT1117-5.0-SOT223")
      (footprint "eagle-import:SOT-223")
      (fields (field (name "MPN") "CJT1117-5.0"))
      (libsource (lib "eagle-import") (part "PMIC-CJT1117-5.0(SOT223)"))
    )
    (comp (ref "U2")
      (value "ATMEGA328P-AU-TQFP32")
      (footprint "eagle-import:TQFP32-0.8-7X7MM")
      (fields (field (name "MPN") "ATMEGA328P-AU"))
      (libsource (lib "eagle-import") (part "MCU-ATMEGA328P-AU(TQFP32)"))
    )
    (comp (ref "USB-TTL")
      (value "PINHD-1X6")
      (footprint "eagle-import:1X06")
      (libsource (lib "eagle-import") (part "PINHD-1X6"))
    )
    (comp (ref "Y1")
      (value "16MHZ")
      (footprint "eagle-import:X2-SMD-5.0X3.2X1.3MM")
      (fields (field (name "MPN") "X053201602002"))
      (libsource (lib "eagle-import") (part "SMD-CRYSTAL-16MHZ-8PF-20PPM-40R(2P-5.0X3.2MM)"))
    )
    (comp (ref "D8")
      (value "YELLOW-0805")
      (footprint "eagle-import:LED-0805")
      (fields (field (name "MPN") "17-215UYC/S530-A3/TR8"))
      (libsource (lib "eagle-import") (part "SMD-LED-CLEAR-YELLOW(0805)"))
    )
    (comp (ref "D9")
      (value "YELLOW-0805")
      (footprint "eagle-import:LED-0805")
      (fields (field (name "MPN") "17-215UYC/S530-A3/TR8"))
      (libsource (lib "eagle-import") (part "SMD-LED-CLEAR-YELLOW(0805)"))
    )
    (comp (ref "D10")
      (value "YELLOW-0805")
      (footprint "eagle-import:LED-0805")
      (fields (field (name "MPN") "17-215UYC/S530-A3/TR8"))
      (libsource (lib "eagle-import") (part "SMD-LED-CLEAR-YELLOW(0805)"))
    )
    (comp (ref "D11")
      (value "YELLOW-0805")
      (footprint "eagle-import:LED-0805")
      (fields (field (name "MPN") "17-215UYC/S530-A3/TR8"))
      (libsource (lib "eagle-import") (part "SMD-LED-CLEAR-YELLOW(0805)"))
    )
    (comp (ref "D12")
      (value "YELLOW-0805")
      (footprint "eagle-import:LED-0805")
      (fields (field (name "MPN") "17-215UYC/S530-A3/TR8"))
      (libsource (lib "eagle-import") (part "SMD-LED-CLEAR-YELLOW(0805)"))
    )
    (comp (ref "D19")
      (value "YELLOW-0805")
      (footprint "eagle-import:LED-0805")
      (fields (field (name "MPN") "17-215UYC/S530-A3/TR8"))
      (libsource (lib "eagle-import") (part "SMD-LED-CLEAR-YELLOW(0805)"))
    )
    (comp (ref "Q3")
      (value "2N7002")
      (footprint "eagle-import:SOT-23")
      (fields (field (name "MPN") "2N7002,215"))
      (libsource (lib "eagle-import") (part "SMD-MOSFET-N-CH-60V-300MA-LOGIC-LEVEL-FET-2N7002(SOT-23)"))
    )
    (comp (ref "R23")
      (value "470")
      (footprint "eagle-import:R0805")
      (fields (field (name "MPN") "RC0805JR-071KL"))
      (libsource (lib "eagle-import") (part "SMD-RES-470R-1%-1/8W(0805)"))
    )
    (comp (ref "R24")
      (value "470")
      (footprint "eagle-import:R0805")
      (fields (field (name "MPN") "RC0805JR-071KL"))
      (libsource (lib "eagle-import") (part "SMD-RES-470R-1%-1/8W(0805)"))
    )
    (comp (ref "R25")
      (value "470")
      (footprint "eagle-import:R0805")
      (fields (field (name "MPN") "RC0805JR-071KL"))
      (libsource (lib "eagle-import") (part "SMD-RES-470R-1%-1/8W(0805)"))
    )
    (comp (ref "R26")
      (value "270")
      (footprint "eagle-import:R0805")
      (fields (field (name "MPN") "RC0805JR-071KL"))
      (libsource (lib "eagle-import") (part "SMD-RES-470R-1%-1/8W(0805)"))
    )
    (comp (ref "R27")
      (value "270")
      (footprint "eagle-import:R0805")
      (fields (field (name "MPN") "RC0805JR-071KL"))
      (libsource (lib "eagle-import") (part "SMD-RES-470R-1%-1/8W(0805)"))
    )
    (comp (ref "R28")
      (value "270")
      (footprint "eagle-import:R0805")
      (fields (field (name "MPN") "RC0805JR-071KL"))
      (libsource (lib "eagle-import") (part "SMD-RES-470R-1%-1/8W(0805)"))
    )
    (comp (ref "R29")
      (value "4.7K")
      (footprint "eagle-import:R0805")
      (fields (field (name "MPN") "RC0805JR-071KL"))
      (libsource (lib "eagle-import") (part "SMD-RES-2.4K-5%-1/8W(0805)"))
    )
    (comp (ref "D32")
      (value "YELLOW-0805")
      (footprint "eagle-import:LED-0805")
      (fields (field (name "MPN") "17-215UYC/S530-A3/TR8"))
      (libsource (lib "eagle-import") (part "SMD-LED-CLEAR-YELLOW(0805)"))
    )
    (comp (ref "D33")
      (value "YELLOW-0805")
      (footprint "eagle-import:LED-0805")
      (fields (field (name "MPN") "17-215UYC/S530-A3/TR8"))
      (libsource (lib "eagle-import") (part "SMD-LED-CLEAR-YELLOW(0805)"))
    )
    (comp (ref "D34")
      (value "YELLOW-0805")
      (footprint "eagle-import:LED-0805")
      (fields (field (name "MPN") "17-215UYC/S530-A3/TR8"))
      (libsource (lib "eagle-import") (part "SMD-LED-CLEAR-YELLOW(0805)"))
    )
    (comp (ref "D35")
      (value "YELLOW-0805")
      (footprint "eagle-import:LED-0805")
      (fields (field (name "MPN") "17-215UYC/S530-A3/TR8"))
      (libsource (lib "eagle-import") (part "SMD-LED-CLEAR-YELLOW(0805)"))
    )
    (comp (ref "D36")
      (value "YELLOW-0805")
      (footprint "eagle-import:LED-0805")
      (fields (field (name "MPN") "17-215UYC/S530-A3/TR8"))
      (libsource (lib "eagle-import") (part "SMD-LED-CLEAR-YELLOW(0805)"))
    )
    (comp (ref "D37")
      (value "YELLOW-0805")
      (footprint "eagle-import:LED-0805")
      (fields (field (name "MPN") "17-215UYC/S530-A3/TR8"))
      (libsource (lib "eagle-import") (part "SMD-LED-CLEAR-YELLOW(0805)"))
    )
    (comp (ref "Q6")
      (value "2N7002")
      (footprint "eagle-import:SOT-23")
      (fields (field (name "MPN") "2N7002,215"))
      (libsource (lib "eagle-import") (part "SMD-MOSFET-N-CH-60V-300MA-LOGIC-LEVEL-FET-2N7002(SOT-23)"))
    )
    (comp (ref "R44")
      (value "470")
      (footprint "eagle-import:R0805")
      (fields (field (name "MPN") "RC0805JR-071KL"))
      (libsource (lib "eagle-import") (part "SMD-RES-470R-1%-1/8W(0805)"))
    )
    (comp (ref "R45")
      (value "470")
      (footprint "eagle-import:R0805")
      (fields (field (name "MPN") "RC0805JR-071KL"))
      (libsource (lib "eagle-import") (part "SMD-RES-470R-1%-1/8W(0805)"))
    )
    (comp (ref "R46")
      (value "470")
      (footprint "eagle-import:R0805")
      (fields (field (name "MPN") "RC0805JR-071KL"))
      (libsource (lib "eagle-import") (part "SMD-RES-470R-1%-1/8W(0805)"))
    )
    (comp (ref "R47")
      (value "270")
      (footprint "eagle-import:R0805")
      (fields (field (name "MPN") "RC0805JR-071KL"))
      (libsource (lib "eagle-import") (part "SMD-RES-470R-1%-1/8W(0805)"))
    )
    (comp (ref "R48")
      (value "270")
      (footprint "eagle-import:R0805")
      (fields (field (name "MPN") "RC0805JR-071KL"))
      (libsource (lib "eagle-import") (part "SMD-RES-470R-1%-1/8W(0805)"))
    )
    (comp (ref "R49")
      (value "270")
      (footprint "eagle-import:R0805")
      (fields (field (name "MPN") "RC0805JR-071KL"))
      (libsource (lib "eagle-import") (part "SMD-RES-470R-1%-1/8W(0805)"))
    )
    (comp (ref "R50")
      (value "4.7K")
      (footprint "eagle-import:R0805")
      (fields (field (name "MPN") "RC0805JR-071KL"))
      (libsource (lib "eagle-import") (part "SMD-RES-2.4K-5%-1/8W(0805)"))
    )
    (comp (ref "D62")
      (value "YELLOW-0805")
      (footprint "eagle-import:LED-0805")
      (fields (field (name "MPN") "17-215UYC/S530-A3/TR8"))
      (libsource (lib "eagle-import") (part "SMD-LED-CLEAR-YELLOW(0805)"))
    )
    (comp (ref "D63")
      (value "YELLOW-0805")
      (footprint "eagle-import:LED-0805")
      (fields (field (name "MPN") "17-215UYC/S530-A3/TR8"))
      (libsource (lib "eagle-import") (part "SMD-LED-CLEAR-YELLOW(0805)"))
    )
    (comp (ref "D64")
      (value "YELLOW-0805")
      (footprint "eagle-import:LED-0805")
      (fields (field (name "MPN") "17-215UYC/S530-A3/TR8"))
      (libsource (lib "eagle-import") (part "SMD-LED-CLEAR-YELLOW(0805)"))
    )
    (comp (ref "D65")
      (value "YELLOW-0805")
      (footprint "eagle-import:LED-0805")
      (fields (field (name "MPN") "17-215UYC/S530-A3/TR8"))
      (libsource (lib "eagle-import") (part "SMD-LED-CLEAR-YELLOW(0805)"))
    )
    (comp (ref "D66")
      (value "YELLOW-0805")
      (footprint "eagle-import:LED-0805")
      (fields (field (name "MPN") "17-215UYC/S530-A3/TR8"))
      (libsource (lib "eagle-import") (part "SMD-LED-CLEAR-YELLOW(0805)"))
    )
    (comp (ref "D67")
      (value "YELLOW-0805")
      (footprint "eagle-import:LED-0805")
      (fields (field (name "MPN") "17-215UYC/S530-A3/TR8"))
      (libsource (lib "eagle-import") (part "SMD-LED-CLEAR-YELLOW(0805)"))
    )
    (comp (ref "Q11")
      (value "2N7002")
      (footprint "eagle-import:SOT-23")
      (fields (field (name "MPN") "2N7002,215"))
      (libsource (lib "eagle-import") (part "SMD-MOSFET-N-CH-60V-300MA-LOGIC-LEVEL-FET-2N7002(SOT-23)"))
    )
    (comp (ref "R79")
      (value "470")
      (footprint "eagle-import:R0805")
      (fields (field (name "MPN") "RC0805JR-071KL"))
      (libsource (lib "eagle-import") (part "SMD-RES-470R-1%-1/8W(0805)"))
    )
    (comp (ref "R80")
      (value "470")
      (footprint "eagle-import:R0805")
      (fields (field (name "MPN") "RC0805JR-071KL"))
      (libsource (lib "eagle-import") (part "SMD-RES-470R-1%-1/8W(0805)"))
    )
    (comp (ref "R81")
      (value "470")
      (footprint "eagle-import:R0805")
      (fields (field (name "MPN") "RC0805JR-071KL"))
      (libsource (lib "eagle-import") (part "SMD-RES-470R-1%-1/8W(0805)"))
    )
    (comp (ref "R82")
      (value "270")
      (footprint "eagle-import:R0805")
      (fields (field (name "MPN") "RC0805JR-071KL"))
      (libsource (lib "eagle-import") (part "SMD-RES-470R-1%-1/8W(0805)"))
    )
    (comp (ref "R83")
      (value "270")
      (footprint "eagle-import:R0805")
      (fields (field (name "MPN") "RC0805JR-071KL"))
      (libsource (lib "eagle-import") (part "SMD-RES-470R-1%-1/8W(0805)"))
    )
    (comp (ref "R84")
      (value "270")
      (footprint "eagle-import:R0805")
      (fields (field (name "MPN") "RC0805JR-071KL"))
      (libsource (lib "eagle-import") (part "SMD-RES-470R-1%-1/8W(0805)"))
    )
    (comp (ref "R85")
      (value "4.7K")
      (footprint "eagle-import:R0805")
      (fields (field (name "MPN") "RC0805JR-071KL"))
      (libsource (lib "eagle-import") (part "SMD-RES-2.4K-5%-1/8W(0805)"))
    )
    (comp (ref "D56")
      (value "YELLOW-0805")
      (footprint "eagle-import:LED-0805")
      (fields (field (name "MPN") "17-215UYC/S530-A3/TR8"))
      (libsource (lib "eagle-import") (part "SMD-LED-CLEAR-YELLOW(0805)"))
    )
    (comp (ref "D57")
      (value "YELLOW-0805")
      (footprint "eagle-import:LED-0805")
      (fields (field (name "MPN") "17-215UYC/S530-A3/TR8"))
      (libsource (lib "eagle-import") (part "SMD-LED-CLEAR-YELLOW(0805)"))
    )
    (comp (ref "D58")
      (value "YELLOW-0805")
      (footprint "eagle-import:LED-0805")
      (fields (field (name "MPN") "17-215UYC/S530-A3/TR8"))
      (libsource (lib "eagle-import") (part "SMD-LED-CLEAR-YELLOW(0805)"))
    )
    (comp (ref "D59")
      (value "YELLOW-0805")
      (footprint "eagle-import:LED-0805")
      (fields (field (name "MPN") "17-215UYC/S530-A3/TR8"))
      (libsource (lib "eagle-import") (part "SMD-LED-CLEAR-YELLOW(0805)"))
    )
    (comp (ref "D60")
      (value "YELLOW-0805")
      (footprint "eagle-import:LED-0805")
      (fields (field (name "MPN") "17-215UYC/S530-A3/TR8"))
      (libsource (lib "eagle-import") (part "SMD-LED-CLEAR-YELLOW(0805)"))
    )
    (comp (ref "D61")
      (value "YELLOW-0805")
      (footprint "eagle-import:LED-0805")
      (fields (field (name "MPN") "17-215UYC/S530-A3/TR8"))
      (libsource (lib "eagle-import") (part "SMD-LED-CLEAR-YELLOW(0805)"))
    )
    (comp (ref "Q10")
      (value "2N7002")
      (footprint "eagle-import:SOT-23")
      (fields (field (name "MPN") "2N7002,215"))
      (libsource (lib "eagle-import") (part "SMD-MOSFET-N-CH-60V-300MA-LOGIC-LEVEL-FET-2N7002(SOT-23)"))
    )
    (comp (ref "R72")
      (value "470")
      (footprint "eagle-import:R0805")
      (fields (field (name "MPN") "RC0805JR-071KL"))
      (libsource (lib "eagle-import") (part "SMD-RES-470R-1%-1/8W(0805)"))
    )
    (comp (ref "R73")
      (value "470")
      (footprint "eagle-import:R0805")
      (fields (field (name "MPN") "RC0805JR-071KL"))
      (libsource (lib "eagle-import") (part "SMD-RES-470R-1%-1/8W(0805)"))
    )
    (comp (ref "R74")
      (value "470")
      (footprint "eagle-import:R0805")
      (fields (field (name "MPN") "RC0805JR-071KL"))
      (libsource (lib "eagle-import") (part "SMD-RES-470R-1%-1/8W(0805)"))
    )
    (comp (ref "R75")
      (value "270")
      (footprint "eagle-import:R0805")
      (fields (field (name "MPN") "RC0805JR-071KL"))
      (libsource (lib "eagle-import") (part "SMD-RES-470R-1%-1/8W(0805)"))
    )
    (comp (ref "R76")
      (value "270")
      (footprint "eagle-import:R0805")
      (fields (field (name "MPN") "RC0805JR-071KL"))
      (libsource (lib "eagle-import") (part "SMD-RES-470R-1%-1/8W(0805)"))
    )
    (comp (ref "R77")
      (value "270")
      (footprint "eagle-import:R0805")
      (fields (field (name "MPN") "RC0805JR-071KL"))
      (libsource (lib "eagle-import") (part "SMD-RES-470R-1%-1/8W(0805)"))
    )
    (comp (ref "R78")
      (value "4.7K")
      (footprint "eagle-import:R0805")
      (fields (field (name "MPN") "RC0805JR-071KL"))
      (libsource (lib "eagle-import") (part "SMD-RES-2.4K-5%-1/8W(0805)"))
    )
    (comp (ref "D2")
      (value "YELLOW-0805")
      (footprint "eagle-import:LED-0805")
      (fields (field (name "MPN") "17-215UYC/S530-A3/TR8"))
      (libsource (lib "eagle-import") (part "SMD-LED-CLEAR-YELLOW(0805)"))
    )
    (comp (ref "D3")
      (value "YELLOW-0805")
      (footprint "eagle-import:LED-0805")
      (fields (field (name "MPN") "17-215UYC/S530-A3/TR8"))
      (libsource (lib "eagle-import") (part "SMD-LED-CLEAR-YELLOW(0805)"))
    )
    (comp (ref "D4")
      (value "YELLOW-0805")
      (footprint "eagle-import:LED-0805")
      (fields (field (name "MPN") "17-215UYC/S530-A3/TR8"))
      (libsource (lib "eagle-import") (part "SMD-LED-CLEAR-YELLOW(0805)"))
    )
    (comp (ref "D5")
      (value "YELLOW-0805")
      (footprint "eagle-import:LED-0805")
      (fields (field (name "MPN") "17-215UYC/S530-A3/TR8"))
      (libsource (lib "eagle-import") (part "SMD-LED-CLEAR-YELLOW(0805)"))
    )
    (comp (ref "D6")
      (value "YELLOW-0805")
      (footprint "eagle-import:LED-0805")
      (fields (field (name "MPN") "17-215UYC/S530-A3/TR8"))
      (libsource (lib "eagle-import") (part "SMD-LED-CLEAR-YELLOW(0805)"))
    )
    (comp (ref "D7")
      (value "YELLOW-0805")
      (footprint "eagle-import:LED-0805")
      (fields (field (name "MPN") "17-215UYC/S530-A3/TR8"))
      (libsource (lib "eagle-import") (part "SMD-LED-CLEAR-YELLOW(0805)"))
    )
    (comp (ref "Q1")
      (value "2N7002")
      (footprint "eagle-import:SOT-23")
      (fields (field (name "MPN") "2N7002,215"))
      (libsource (lib "eagle-import") (part "SMD-MOSFET-N-CH-60V-300MA-LOGIC-LEVEL-FET-2N7002(SOT-23)"))
    )
    (comp (ref "R10")
      (value "470")
      (footprint "eagle-import:R0805")
      (fields (field (name "MPN") "RC0805JR-071KL"))
      (libsource (lib "eagle-import") (part "SMD-RES-470R-1%-1/8W(0805)"))
    )
    (comp (ref "R11")
      (value "470")
      (footprint "eagle-import:R0805")
      (fields (field (name "MPN") "RC0805JR-071KL"))
      (libsource (lib "eagle-import") (part "SMD-RES-470R-1%-1/8W(0805)"))
    )
    (comp (ref "R12")
      (value "470")
      (footprint "eagle-import:R0805")
      (fields (field (name "MPN") "RC0805JR-071KL"))
      (libsource (lib "eagle-import") (part "SMD-RES-470R-1%-1/8W(0805)"))
    )
    (comp (ref "R13")
      (value "270")
      (footprint "eagle-import:R0805")
      (fields (field (name "MPN") "RC0805JR-071KL"))
      (libsource (lib "eagle-import") (part "SMD-RES-470R-1%-1/8W(0805)"))
    )
    (comp (ref "R14")
      (value "270")
      (footprint "eagle-import:R0805")
      (fields (field (name "MPN") "RC0805JR-071KL"))
      (libsource (lib "eagle-import") (part "SMD-RES-470R-1%-1/8W(0805)"))
    )
    (comp (ref "R15")
      (value "270")
      (footprint "eagle-import:R0805")
      (fields (field (name "MPN") "RC0805JR-071KL"))
      (libsource (lib "eagle-import") (part "SMD-RES-470R-1%-1/8W(0805)"))
    )
    (comp (ref "R16")
      (value "4.7K")
      (footprint "eagle-import:R0805")
      (fields (field (name "MPN") "RC0805JR-071KL"))
      (libsource (lib "eagle-import") (part "SMD-RES-2.4K-5%-1/8W(0805)"))
    )
  )
  (nets
    (net (code "1") (name "+5V") (class "Default")
      (node (ref "C3") (pin "2") (pinfunction "2_2") (pintype "passive"))
      (node (ref "C6") (pin "2") (pinfunction "2_2") (pintype "passive"))
      (node (ref "C7") (pin "2") (pinfunction "2_2") (pintype "passive"))
      (node (ref "CT2") (pin "+") (pinfunction "+_+") (pintype "passive"))
      (node (ref "D1") (pin "-") (pinfunction "2_-") (pintype "bidirectional"))
      (node (ref "ICSP") (pin "2") (pinfunction "2_2") (pintype "passive"))
      (node (ref "R") (pin "2") (pinfunction "2_2") (pintype "passive"))
      (node (ref "R10") (pin "1") (pinfunction "1_1") (pintype "passive"))
      (node (ref "R11") (pin "1") (pinfunction "1_1") (pintype "passive"))
      (node (ref "R12") (pin "1") (pinfunction "1_1") (pintype "passive"))
      (node (ref "R13") (pin "1") (pinfunction "1_1") (pintype "passive"))
      (node (ref "R14") (pin "1") (pinfunction "1_1") (pintype "passive"))
      (node (ref "R15") (pin "1") (pinfunction "1_1") (pintype "passive"))
      (node (ref "R17") (pin "1") (pinfunction "1_1") (pintype "passive"))
      (node (ref "R18") (pin "1") (pinfunction "1_1") (pintype "passive"))
      (node (ref "R19") (pin "1") (pinfunction "1_1") (pintype "passive"))
      (node (ref "R20") (pin "1") (pinfunction "1_1") (pintype "passive"))
      (node (ref "R21") (pin "1") (pinfunction "1_1") (pintype "passive"))
      (node (ref "R22") (pin "1") (pinfunction "1_1") (pintype "passive"))
      (node (ref "R23") (pin "1") (pinfunction "1_1") (pintype "passive"))
      (node (ref "R24") (pin "1") (pinfunction "1_1") (pintype "passive"))
      (node (ref "R25") (pin "1") (pinfunction "1_1") (pintype "passive"))
      (node (ref "R26") (pin "1") (pinfunction "1_1") (pintype "passive"))
      (node (ref "R27") (pin "1") (pinfunction "1_1") (pintype "passive"))
      (node (ref "R28") (pin "1") (pinfunction "1_1") (pintype "passive"))
      (node (ref "R30") (pin "1") (pinfunction "1_1") (pintype "passive"))
      (node (ref "R31") (pin "1") (pinfunction "1_1") (pintype "passive"))
      (node (ref "R32") (pin "1") (pinfunction "1_1") (pintype "passive"))
      (node (ref "R33") (pin "1") (pinfunction "1_1") (pintype "passive"))
      (node (ref "R34") (pin "1") (pinfunction "1_1") (pintype "passive"))
      (node (ref "R35") (pin "1") (pinfunction "1_1") (pintype "passive"))
      (node (ref "R37") (pin "1") (pinfunction "1_1") (pintype "passive"))
      (node (ref "R38") (pin "1") (pinfunction "1_1") (pintype "passive"))
      (node (ref "R39") (pin "1") (pinfunction "1_1") (pintype "passive"))
      (node (ref "R40") (pin "1") (pinfunction "1_1") (pintype "passive"))
      (node (ref "R41") (pin "1") (pinfunction "1_1") (pintype "passive"))
      (node (ref "R42") (pin "1") (pinfunction "1_1") (pintype "passive"))
      (node (ref "R44") (pin "1") (pinfunction "1_1") (pintype "passive"))
      (node (ref "R45") (pin "1") (pinfunction "1_1") (pintype "passive"))
      (node (ref "R46") (pin "1") (pinfunction "1_1") (pintype "passive"))
      (node (ref "R47") (pin "1") (pinfunction "1_1") (pintype "passive"))
      (node (ref "R48") (pin "1") (pinfunction "1_1") (pintype "passive"))
      (node (ref "R49") (pin "1") (pinfunction "1_1") (pintype "passive"))
      (node (ref "R51") (pin "1") (pinfunction "1_1") (pintype "passive"))
      (node (ref "R52") (pin "1") (pinfunction "1_1") (pintype "passive"))
      (node (ref "R53") (pin "1") (pinfunction "1_1") (pintype "passive"))
      (node (ref "R54") (pin "1") (pinfunction "1_1") (pintype "passive"))
      (node (ref "R55") (pin "1") (pinfunction "1_1") (pintype "passive"))
      (node (ref "R56") (pin "1") (pinfunction "1_1") (pintype "passive"))
      (node (ref "R58") (pin "1") (pinfunction "1_1") (pintype "passive"))
      (node (ref "R59") (pin "1") (pinfunction "1_1") (pintype "passive"))
      (node (ref "R60") (pin "1") (pinfunction "1_1") (pintype "passive"))
      (node (ref "R61") (pin "1") (pinfunction "1_1") (pintype "passive"))
      (node (ref "R62") (pin "1") (pinfunction "1_1") (pintype "passive"))
      (node (ref "R63") (pin "1") (pinfunction "1_1") (pintype "passive"))
      (node (ref "R65") (pin "1") (pinfunction "1_1") (pintype "passive"))
      (node (ref "R66") (pin "1") (pinfunction "1_1") (pintype "passive"))
      (node (ref "R67") (pin "1") (pinfunction "1_1") (pintype "passive"))
      (node (ref "R68") (pin "1") (pinfunction "1_1") (pintype "passive"))
      (node (ref "R69") (pin "1") (pinfunction "1_1") (pintype "passive"))
      (node (ref "R7") (pin "2") (pinfunction "2_2") (pintype "passive"))
      (node (ref "R70") (pin "1") (pinfunction "1_1") (pintype "passive"))
      (node (ref "R72") (pin "1") (pinfunction "1_1") (pintype "passive"))
      (node (ref "R73") (pin "1") (pinfunction "1_1") (pintype "passive"))
      (node (ref "R74") (pin "1") (pinfunction "1_1") (pintype "passive"))
      (node (ref "R75") (pin "1") (pinfunction "1_1") (pintype "passive"))
      (node (ref "R76") (pin "1") (pinfunction "1_1") (pintype "passive"))
      (node (ref "R77") (pin "1") (pinfunction "1_1") (pintype "passive"))
      (node (ref "R79") (pin "1") (pinfunction "1_1") (pintype "passive"))
      (node (ref "R80") (pin "1") (pinfunction "1_1") (pintype "passive"))
      (node (ref "R81") (pin "1") (pinfunction "1_1") (pintype "passive"))
      (node (ref "R82") (pin "1") (pinfunction "1_1") (pintype "passive"))
      (node (ref "R83") (pin "1") (pinfunction "1_1") (pintype "passive"))
      (node (ref "R84") (pin "1") (pinfunction "1_1") (pintype "passive"))
      (node (ref "R86") (pin "1") (pinfunction "1_1") (pintype "passive"))
      (node (ref "R87") (pin "1") (pinfunction "1_1") (pintype "passive"))
      (node (ref "R88") (pin "1") (pinfunction "1_1") (pintype "passive"))
      (node (ref "R89") (pin "1") (pinfunction "1_1") (pintype "passive"))
      (node (ref "R90") (pin "1") (pinfunction "1_1") (pintype "passive"))
      (node (ref "R91") (pin "1") (pinfunction "1_1") (pintype "passive"))
      (node (ref "R93") (pin "1") (pinfunction "1_1") (pintype "passive"))
      (node (ref "R94") (pin "1") (pinfunction "1_1") (pintype "passive"))
      (node (ref "R95") (pin "1") (pinfunction "1_1") (pintype "passive"))
      (node (ref "R96") (pin "1") (pinfunction "1_1") (pintype "passive"))
      (node (ref "R97") (pin "1") (pinfunction "1_1") (pintype "passive"))
      (node (ref "R98") (pin "1") (pinfunction "1_1") (pintype "passive"))
      (node (ref "U1") (pin "2") (pinfunction "OUT_2") (pintype "bidirectional"))
      (node (ref "U1") (pin "TER") (pinfunction "OUT_TER") (pintype "bidirectional"))
      (node (ref "U2") (pin "18") (pinfunction "AVCC_18") (pintype "bidirectional"))
      (node (ref "U2") (pin "4") (pinfunction "VCC_4") (pintype "bidirectional"))
      (node (ref "U2") (pin "6") (pinfunction "VCC_6") (pintype "bidirectional"))
      (node (ref "USB-TTL") (pin "4") (pinfunction "4_4") (pintype "passive"))
    )
    (net (code "2") (name "9V") (class "Default")
      (node (ref "C1") (pin "2") (pinfunction "2_2") (pintype "passive"))
      (node (ref "C8") (pin "2") (pinfunction "2_2") (pintype "passive"))
      (node (ref "CT1") (pin "+") (pinfunction "+_+") (pintype "passive"))
      (node (ref "F1") (pin "1") (pinfunction "1_1") (pintype "passive"))
      (node (ref "RJ45") (pin "2-1") (pinfunction "1_2-1") (pintype "passive"))
      (node (ref "RJ45") (pin "2-2") (pinfunction "2_2-2") (pintype "passive"))
      (node (ref "U1") (pin "3") (pinfunction "IN_3") (pintype "bidirectional"))
    )
    (net (code "3") (name "9VSUPPLY") (class "Default")
      (node (ref "F1") (pin "2") (pinfunction "2_2") (pintype "passive"))
      (node (ref "J5") (pin "2") (pinfunction "2_2") (pintype "bidirectional"))
      (node (ref "RJ45") (pin "1-1") (pinfunction "1_1-1") (pintype "passive"))
      (node (ref "RJ45") (pin "1-2") (pinfunction "2_1-2") (pintype "passive"))
    )
    (net (code "4") (name "AUX1") (class "Default")
      (node (ref "RJ45") (pin "1-5") (pinfunction "5_1-5") (pintype "passive"))
      (node (ref "RJ45") (pin "2-5") (pinfunction "5_2-5") (pintype "passive"))
      (node (ref "U2") (pin "19") (pinfunction "ADC6_19") (pintype "bidirectional"))
    )
    (net (code "5") (name "AUX2") (class "Default")
      (node (ref "RJ45") (pin "1-6") (pinfunction "6_1-6") (pintype "passive"))
      (node (ref "RJ45") (pin "2-6") (pinfunction "6_2-6") (pintype "passive"))
      (node (ref "U2") (pin "22") (pinfunction "ADC7_22") (pintype "bidirectional"))
    )
    (net (code "6") (name "BROWN") (class "Default")
      (node (ref "USB-TTL") (pin "5") (pinfunction "5_5") (pintype "passive"))
    )
    (net (code "7") (name "GND") (class "Default")
      (node (ref "C1") (pin "1") (pinfunction "1_1") (pintype "passive"))
      (node (ref "C2") (pin "1") (pinfunction "1_1") (pintype "passive"))
      (node (ref "C3") (pin "1") (pinfunction "1_1") (pintype "passive"))
      (node (ref "C4") (pin "1") (pinfunction "1_1") (pintype "passive"))
      (node (ref "C6") (pin "1") (pinfunction "1_1") (pintype "passive"))
      (node (ref "C7") (pin "1") (pinfunction "1_1") (pintype "passive"))
      (node (ref "C8") (pin "1") (pinfunction "1_1") (pintype "passive"))
      (node (ref "CT1") (pin "-") (pinfunction "-_-") (pintype "passive"))
      (node (ref "CT2") (pin "-") (pinfunction "-_-") (pintype "passive"))
      (node (ref "D1") (pin "+") (pinfunction "1_+") (pintype "bidirectional"))
      (node (ref "ICSP") (pin "6") (pinfunction "6_6") (pintype "passive"))
      (node (ref "J2") (pin "1") (pinfunction "1_1") (pintype "passive"))
      (node (ref "J3") (pin "1") (pinfunction "1_1") (pintype "passive"))
      (node (ref "J4") (pin "1") (pinfunction "1_1") (pintype "passive"))
      (node (ref "J5") (pin "4") (pinfunction "4_4") (pintype "bidirectional"))
      (node (ref "Q1") (pin "2") (pinfunction "S_2") (pintype "passive"))
      (node (ref "Q10") (pin "2") (pinfunction "S_2") (pintype "passive"))
      (node (ref "Q11") (pin "2") (pinfunction "S_2") (pintype "passive"))
      (node (ref "Q12") (pin "2") (pinfunction "S_2") (pintype "passive"))
      (node (ref "Q13") (pin "2") (pinfunction "S_2") (pintype "passive"))
      (node (ref "Q2") (pin "2") (pinfunction "S_2") (pintype "passive"))
      (node (ref "Q3") (pin "2") (pinfunction "S_2") (pintype "passive"))
      (node (ref "Q4") (pin "2") (pinfunction "S_2") (pintype "passive"))
      (node (ref "Q5") (pin "2") (pinfunction "S_2") (pintype "passive"))
      (node (ref "Q6") (pin "2") (pinfunction "S_2") (pintype "passive"))
      (node (ref "Q7") (pin "2") (pinfunction "S_2") (pintype "passive"))
      (node (ref "Q8") (pin "2") (pinfunction "S_2") (pintype "passive"))
      (node (ref "Q9") (pin "2") (pinfunction "S_2") (pintype "passive"))
      (node (ref "R100") (pin "1") (pinfunction "1_1") (pintype "passive"))
      (node (ref "R16") (pin "2") (pinfunction "2_2") (pintype "passive"))
      (node (ref "R29") (pin "2") (pinfunction "2_2") (pintype "passive"))
      (node (ref "R3") (pin "1") (pinfunction "1_1") (pintype "passive"))
      (node (ref "R36") (pin "2") (pinfunction "2_2") (pintype "passive"))
      (node (ref "R4") (pin "2") (pinfunction "2_2") (pintype "passive"))
      (node (ref "R43") (pin "2") (pinfunction "2_2") (pintype "passive"))
      (node (ref "R50") (pin "2") (pinfunction "2_2") (pintype "passive"))
      (node (ref "R57") (pin "2") (pinfunction "2_2") (pintype "passive"))
      (node (ref "R64") (pin "2") (pinfunction "2_2") (pintype "passive"))
      (node (ref "R71") (pin "2") (pinfunction "2_2") (pintype "passive"))
      (node (ref "R78") (pin "2") (pinfunction "2_2") (pintype "passive"))
      (node (ref "R85") (pin "2") (pinfunction "2_2") (pintype "passive"))
      (node (ref "R92") (pin "2") (pinfunction "2_2") (pintype "passive"))
      (node (ref "R99") (pin "2") (pinfunction "2_2") (pintype "passive"))
      (node (ref "RJ45") (pin "1-7") (pinfunction "7_1-7") (pintype "passive"))
      (node (ref "RJ45") (pin "1-8") (pinfunction "8_1-8") (pintype "passive"))
      (node (ref "RJ45") (pin "2-7") (pinfunction "7_2-7") (pintype "passive"))
      (node (ref "RJ45") (pin "2-8") (pinfunction "8_2-8") (pintype "passive"))
      (node (ref "RJ45") (pin "G1") (pinfunction "S2_G1") (pintype "passive"))
      (node (ref "RJ45") (pin "G3") (pinfunction "S1_G3") (pintype "passive"))
      (node (ref "RX") (pin "-") (pinfunction "-_-") (pintype "passive"))
      (node (ref "SW1") (pin "2") (pinfunction "2_2") (pintype "bidirectional"))
      (node (ref "TX") (pin "-") (pinfunction "-_-") (pintype "passive"))
      (node (ref "U1") (pin "1") (pinfunction "GND_1") (pintype "bidirectional"))
      (node (ref "U2") (pin "21") (pinfunction "GND_21") (pintype "bidirectional"))
      (node (ref "U2") (pin "3") (pinfunction "GND_3") (pintype "bidirectional"))
      (node (ref "U2") (pin "5") (pinfunction "GND_5") (pintype "bidirectional"))
      (node (ref "USB-TTL") (pin "6") (pinfunction "6_6") (pintype "passive"))
    )
    (net (code "8") (name "GREEN") (class "Default")
      (node (ref "C5") (pin "2") (pinfunction "2_2") (pintype "passive"))
      (node (ref "USB-TTL") (pin "1") (pinfunction "1_1") (pintype "passive"))
    )
    (net (code "9") (name "LED1") (class "Default")
      (node (ref "Q2") (pin "1") (pinfunction "G_1") (pintype "passive"))
      (node (ref "R4") (pin "1") (pinfunction "1_1") (pintype "passive"))
      (node (ref "U2") (pin "2") (pinfunction "PD4(XCK/T0)_2") (pintype "bidirectional"))
    )
    (net (code "10") (name "LED2") (class "Default")
      (node (ref "Q1") (pin "1") (pinfunction "G_1") (pintype "passive"))
      (node (ref "R16") (pin "1") (pinfunction "1_1") (pintype "passive"))
      (node (ref "U2") (pin "9") (pinfunction "PD5(T1)_9") (pintype "bidirectional"))
    )
    (net (code "11") (name "LED3") (class "Default")
      (node (ref "Q3") (pin "1") (pinfunction "G_1") (pintype "passive"))
      (node (ref "R29") (pin "1") (pinfunction "1_1") (pintype "passive"))
      (node (ref "U2") (pin "10") (pinfunction "PD6(AIN0)_10") (pintype "bidirectional"))
    )
    (net (code "12") (name "LED4") (class "Default")
      (node (ref "Q4") (pin "1") (pinfunction "G_1") (pintype "passive"))
      (node (ref "R36") (pin "1") (pinfunction "1_1") (pintype "passive"))
      (node (ref "U2") (pin "11") (pinfunction "PD7(AIN1)_11") (pintype "bidirectional"))
    )
    (net (code "13") (name "LED5") (class "Default")
      (node (ref "Q5") (pin "1") (pinfunction "G_1") (pintype "passive"))
      (node (ref "R43") (pin "1") (pinfunction "1_1") (pintype "passive"))
      (node (ref "U2") (pin "12") (pinfunction "PB0(ICP)_12") (pintype "bidirectional"))
    )
    (net (code "14") (name "LED6") (class "Default")
      (node (ref "Q6") (pin "1") (pinfunction "G_1") (pintype "passive"))
      (node (ref "R50") (pin "1") (pinfunction "1_1") (pintype "passive"))
      (node (ref "U2") (pin "13") (pinfunction "PB1(OC1A)_13") (pintype "bidirectional"))
    )
    (net (code "15") (name "LED7") (class "Default")
      (node (ref "Q7") (pin "1") (pinfunction "G_1") (pintype "passive"))
      (node (ref "R57") (pin "1") (pinfunction "1_1") (pintype "passive"))
      (node (ref "U2") (pin "14") (pinfunction "PB2(SS/OC1B)_14") (pintype "bidirectional"))
    )
    (net (code "16") (name "LED8") (class "Default")
      (node (ref "ICSP") (pin "4") (pinfunction "4_4") (pintype "passive"))
      (node (ref "Q8") (pin "1") (pinfunction "G_1") (pintype "passive"))
      (node (ref "R64") (pin "1") (pinfunction "1_1") (pintype "passive"))
      (node (ref "U2") (pin "15") (pinfunction "PB3(MOSI/OC2)_15") (pintype "bidirectional"))
    )
    (net (code "17") (name "LED9") (class "Default")
      (node (ref "ICSP") (pin "1") (pinfunction "1_1") (pintype "passive"))
      (node (ref "Q9") (pin "1") (pinfunction "G_1") (pintype "passive"))
      (node (ref "R71") (pin "1") (pinfunction "1_1") (pintype "passive"))
      (node (ref "U2") (pin "16") (pinfunction "PB4(MISO)_16") (pintype "bidirectional"))
    )
    (net (code "18") (name "LED10") (class "Default")
      (node (ref "ICSP") (pin "3") (pinfunction "3_3") (pintype "passive"))
      (node (ref "Q10") (pin "1") (pinfunction "G_1") (pintype "passive"))
      (node (ref "R78") (pin "1") (pinfunction "1_1") (pintype "passive"))
      (node (ref "U2") (pin "17") (pinfunction "PB5(SCK)_17") (pintype "bidirectional"))
    )
    (net (code "19") (name "LED11") (class "Default")
      (node (ref "Q11") (pin "1") (pinfunction "G_1") (pintype "passive"))
      (node (ref "R85") (pin "1") (pinfunction "1_1") (pintype "passive"))
      (node (ref "U2") (pin "26") (pinfunction "PC3(ADC3)_26") (pintype "bidirectional"))
    )
    (net (code "20") (name "LED12") (class "Default")
      (node (ref "Q12") (pin "1") (pinfunction "G_1") (pintype "passive"))
      (node (ref "R92") (pin "1") (pinfunction "1_1") (pintype "passive"))
      (node (ref "U2") (pin "27") (pinfunction "PC4(ADC4/SDA)_27") (pintype "bidirectional"))
    )
    (net (code "21") (name "LED13") (class "Default")
      (node (ref "Q13") (pin "1") (pinfunction "G_1") (pintype "passive"))
      (node (ref "R99") (pin "1") (pinfunction "1_1") (pintype "passive"))
      (node (ref "U2") (pin "28") (pinfunction "PC5(ADC5/SCL)_28") (pintype "bidirectional"))
    )
    (net (code "22") (name "Net-(D2-Pad+)") (class "Default")
      (node (ref "D2") (pin "+") (pinfunction "+_+") (pintype "passive"))
      (node (ref "R10") (pin "2") (pinfunction "2_2") (pintype "passive"))
    )
    (net (code "23") (name "Net-(D3-Pad+)") (class "Default")
      (node (ref "D3") (pin "+") (pinfunction "+_+") (pintype "passive"))
      (node (ref "R11") (pin "2") (pinfunction "2_2") (pintype "passive"))
    )
    (net (code "24") (name "Net-(D4-Pad+)") (class "Default")
      (node (ref "D4") (pin "+") (pinfunction "+_+") (pintype "passive"))
      (node (ref "R12") (pin "2") (pinfunction "2_2") (pintype "passive"))
    )
    (net (code "25") (name "Net-(D5-Pad+)") (class "Default")
      (node (ref "D5") (pin "+") (pinfunction "+_+") (pintype "passive"))
      (node (ref "R13") (pin "2") (pinfunction "2_2") (pintype "passive"))
    )
    (net (code "26") (name "Net-(D6-Pad+)") (class "Default")
      (node (ref "D6") (pin "+") (pinfunction "+_+") (pintype "passive"))
      (node (ref "R14") (pin "2") (pinfunction "2_2") (pintype "passive"))
    )
    (net (code "27") (name "Net-(D7-Pad+)") (class "Default")
      (node (ref "D7") (pin "+") (pinfunction "+_+") (pintype "passive"))
      (node (ref "R15") (pin "2") (pinfunction "2_2") (pintype "passive"))
    )
    (net (code "28") (name "Net-(D8-Pad+)") (class "Default")
      (node (ref "D8") (pin "+") (pinfunction "+_+") (pintype "passive"))
      (node (ref "R23") (pin "2") (pinfunction "2_2") (pintype "passive"))
    )
    (net (code "29") (name "Net-(D9-Pad+)") (class "Default")
      (node (ref "D9") (pin "+") (pinfunction "+_+") (pintype "passive"))
      (node (ref "R24") (pin "2") (pinfunction "2_2") (pintype "passive"))
    )
    (net (code "30") (name "Net-(D10-Pad+)") (class "Default")
      (node (ref "D10") (pin "+") (pinfunction "+_+") (pintype "passive"))
      (node (ref "R25") (pin "2") (pinfunction "2_2") (pintype "passive"))
    )
    (net (code "31") (name "Net-(D11-Pad+)") (class "Default")
      (node (ref "D11") (pin "+") (pinfunction "+_+") (pintype "passive"))
      (node (ref "R26") (pin "2") (pinfunction "2_2") (pintype "passive"))
    )
    (net (code "32") (name "Net-(D12-Pad+)") (class "Default")
      (node (ref "D12") (pin "+") (pinfunction "+_+") (pintype "passive"))
      (node (ref "R27") (pin "2") (pinfunction "2_2") (pintype "passive"))
    )
    (net (code "33") (name "Net-(D13-Pad+)") (class "Default")
      (node (ref "D13") (pin "+") (pinfunction "+_+") (pintype "passive"))
      (node (ref "R17") (pin "2") (pinfunction "2_2") (pintype "passive"))
    )
    (net (code "34") (name "Net-(D14-Pad+)") (class "Default")
      (node (ref "D14") (pin "+") (pinfunction "+_+") (pintype "passive"))
      (node (ref "R18") (pin "2") (pinfunction "2_2") (pintype "passive"))
    )
    (net (code "35") (name "Net-(D15-Pad+)") (class "Default")
      (node (ref "D15") (pin "+") (pinfunction "+_+") (pintype "passive"))
      (node (ref "R19") (pin "2") (pinfunction "2_2") (pintype "passive"))
    )
    (net (code "36") (name "Net-(D16-Pad+)") (class "Default")
      (node (ref "D16") (pin "+") (pinfunction "+_+") (pintype "passive"))
      (node (ref "R20") (pin "2") (pinfunction "2_2") (pintype "passive"))
    )
    (net (code "37") (name "Net-(D17-Pad+)") (class "Default")
      (node (ref "D17") (pin "+") (pinfunction "+_+") (pintype "passive"))
      (node (ref "R21") (pin "2") (pinfunction "2_2") (pintype "passive"))
    )
    (net (code "38") (name "Net-(D18-Pad+)") (class "Default")
      (node (ref "D18") (pin "+") (pinfunction "+_+") (pintype "passive"))
      (node (ref "R22") (pin "2") (pinfunction "2_2") (pintype "passive"))
    )
    (net (code "39") (name "Net-(D19-Pad+)") (class "Default")
      (node (ref "D19") (pin "+") (pinfunction "+_+") (pintype "passive"))
      (node (ref "R28") (pin "2") (pinfunction "2_2") (pintype "passive"))
    )
    (net (code "40") (name "Net-(D20-Pad+)") (class "Default")
      (node (ref "D20") (pin "+") (pinfunction "+_+") (pintype "passive"))
      (node (ref "R30") (pin "2") (pinfunction "2_2") (pintype "passive"))
    )
    (net (code "41") (name "Net-(D21-Pad+)") (class "Default")
      (node (ref "D21") (pin "+") (pinfunction "+_+") (pintype "passive"))
      (node (ref "R31") (pin "2") (pinfunction "2_2") (pintype "passive"))
    )
    (net (code "42") (name "Net-(D22-Pad+)") (class "Default")
      (node (ref "D22") (pin "+") (pinfunction "+_+") (pintype "passive"))
      (node (ref "R32") (pin "2") (pinfunction "2_2") (pintype "passive"))
    )
    (net (code "43") (name "Net-(D23-Pad+)") (class "Default")
      (node (ref "D23") (pin "+") (pinfunction "+_+") (pintype "passive"))
      (node (ref "R33") (pin "2") (pinfunction "2_2") (pintype "passive"))
    )
    (net (code "44") (name "Net-(D24-Pad+)") (class "Default")
      (node (ref "D24") (pin "+") (pinfunction "+_+") (pintype "passive"))
      (node (ref "R34") (pin "2") (pinfunction "2_2") (pintype "passive"))
    )
    (net (code "45") (name "Net-(D25-Pad+)") (class "Default")
      (node (ref "D25") (pin "+") (pinfunction "+_+") (pintype "passive"))
      (node (ref "R35") (pin "2") (pinfunction "2_2") (pintype "passive"))
    )
    (net (code "46") (name "Net-(D26-Pad+)") (class "Default")
      (node (ref "D26") (pin "+") (pinfunction "+_+") (pintype "passive"))
      (node (ref "R37") (pin "2") (pinfunction "2_2") (pintype "passive"))
    )
    (net (code "47") (name "Net-(D27-Pad+)") (class "Default")
      (node (ref "D27") (pin "+") (pinfunction "+_+") (pintype "passive"))
      (node (ref "R38") (pin "2") (pinfunction "2_2") (pintype "passive"))
    )
    (net (code "48") (name "Net-(D28-Pad+)") (class "Default")
      (node (ref "D28") (pin "+") (pinfunction "+_+") (pintype "passive"))
      (node (ref "R39") (pin "2") (pinfunction "2_2") (pintype "passive"))
    )
    (net (code "49") (name "Net-(D29-Pad+)") (class "Default")
      (node (ref "D29") (pin "+") (pinfunction "+_+") (pintype "passive"))
      (node (ref "R40") (pin "2") (pinfunction "2_2") (pintype "passive"))
    )
    (net (code "50") (name "Net-(D30-Pad+)") (class "Default")
      (node (ref "D30") (pin "+") (pinfunction "+_+") (pintype "passive"))
      (node (ref "R41") (pin "2") (pinfunction "2_2") (pintype "passive"))
    )
    (net (code "51") (name "Net-(D31-Pad+)") (class "Default")
      (node (ref "D31") (pin "+") (pinfunction "+_+") (pintype "passive"))
      (node (ref "R42") (pin "2") (pinfunction "2_2") (pintype "passive"))
    )
    (net (code "52") (name "Net-(D32-Pad+)") (class "Default")
      (node (ref "D32") (pin "+") (pinfunction "+_+") (pintype "passive"))
      (node (ref "R44") (pin "2") (pinfunction "2_2") (pintype "passive"))
    )
    (net (code "53") (name "Net-(D33-Pad+)") (class "Default")
      (node (ref "D33") (pin "+") (pinfunction "+_+") (pintype "passive"))
      (node (ref "R45") (pin "2") (pinfunction "2_2") (pintype "passive"))
    )
    (net (code "54") (name "Net-(D34-Pad+)") (class "Default")
      (node (ref "D34") (pin "+") (pinfunction "+_+") (pintype "passive"))
      (node (ref "R46") (pin "2") (pinfunction "2_2") (pintype "passive"))
    )
    (net (code "55") (name "Net-(D35-Pad+)") (class "Default")
      (node (ref "D35") (pin "+") (pinfunction "+_+") (pintype "passive"))
      (node (ref "R47") (pin "2") (pinfunction "2_2") (pintype "passive"))
    )
    (net (code "56") (name "Net-(D36-Pad+)") (class "Default")
      (node (ref "D36") (pin "+") (pinfunction "+_+") (pintype "passive"))
      (node (ref "R48") (pin "2") (pinfunction "2_2") (pintype "passive"))
    )
    (net (code "57") (name "Net-(D37-Pad+)") (class "Default")
      (node (ref "D37") (pin "+") (pinfunction "+_+") (pintype "passive"))
      (node (ref "R49") (pin "2") (pinfunction "2_2") (pintype "passive"))
    )
    (net (code "58") (name "Net-(D38-Pad+)") (class "Default")
      (node (ref "D38") (pin "+") (pinfunction "+_+") (pintype "passive"))
      (node (ref "R51") (pin "2") (pinfunction "2_2") (pintype "passive"))
    )
    (net (code "59") (name "Net-(D39-Pad+)") (class "Default")
      (node (ref "D39") (pin "+") (pinfunction "+_+") (pintype "passive"))
      (node (ref "R52") (pin "2") (pinfunction "2_2") (pintype "passive"))
    )
    (net (code "60") (name "Net-(D40-Pad+)") (class "Default")
      (node (ref "D40") (pin "+") (pinfunction "+_+") (pintype "passive"))
      (node (ref "R53") (pin "2") (pinfunction "2_2") (pintype "passive"))
    )
    (net (code "61") (name "Net-(D41-Pad+)") (class "Default")
      (node (ref "D41") (pin "+") (pinfunction "+_+") (pintype "passive"))
      (node (ref "R54") (pin "2") (pinfunction "2_2") (pintype "passive"))
    )
    (net (code "62") (name "Net-(D42-Pad+)") (class "Default")
      (node (ref "D42") (pin "+") (pinfunction "+_+") (pintype "passive"))
      (node (ref "R55") (pin "2") (pinfunction "2_2") (pintype "passive"))
    )
    (net (code "63") (name "Net-(D43-Pad+)") (class "Default")
      (node (ref "D43") (pin "+") (pinfunction "+_+") (pintype "passive"))
      (node (ref "R56") (pin "2") (pinfunction "2_2") (pintype "passive"))
    )
    (net (code "64") (name "Net-(D44-Pad+)") (class "Default")
      (node (ref "D44") (pin "+") (pinfunction "+_+") (pintype "passive"))
      (node (ref "R58") (pin "2") (pinfunction "2_2") (pintype "passive"))
    )
    (net (code "65") (name "Net-(D45-Pad+)") (class "Default")
      (node (ref "D45") (pin "+") (pinfunction "+_+") (pintype "passive"))
      (node (ref "R59") (pin "2") (pinfunction "2_2") (pintype "passive"))
    )
    (net (code "66") (name "Net-(D46-Pad+)") (class "Default")
      (node (ref "D46") (pin "+") (pinfunction "+_+") (pintype "passive"))
      (node (ref "R60") (pin "2") (pinfunction "2_2") (pintype "passive"))
    )
    (net (code "67") (name "Net-(D47-Pad+)") (class "Default")
      (node (ref "D47") (pin "+") (pinfunction "+_+") (pintype "passive"))
      (node (ref "R61") (pin "2") (pinfunction "2_2") (pintype "passive"))
    )
    (net (code "68") (name "Net-(D48-Pad+)") (class "Default")
      (node (ref "D48") (pin "+") (pinfunction "+_+") (pintype "passive"))
      (node (ref "R62") (pin "2") (pinfunction "2_2") (pintype "passive"))
    )
    (net (code "69") (name "Net-(D49-Pad+)") (class "Default")
      (node (ref "D49") (pin "+") (pinfunction "+_+") (pintype "passive"))
      (node (ref "R63") (pin "2") (pinfunction "2_2") (pintype "passive"))
    )
    (net (code "70") (name "Net-(D50-Pad+)") (class "Default")
      (node (ref "D50") (pin "+") (pinfunction "+_+") (pintype "passive"))
      (node (ref "R65") (pin "2") (pinfunction "2_2") (pintype "passive"))
    )
    (net (code "71") (name "Net-(D51-Pad+)") (class "Default")
      (node (ref "D51") (pin "+") (pinfunction "+_+") (pintype "passive"))
      (node (ref "R66") (pin "2") (pinfunction "2_2") (pintype "passive"))
    )
    (net (code "72") (name "Net-(D52-Pad+)") (class "Default")
      (node (ref "D52") (pin "+") (pinfunction "+_+") (pintype "passive"))
      (node (ref "R67") (pin "2") (pinfunction "2_2") (pintype "passive"))
    )
    (net (code "73") (name "Net-(D53-Pad+)") (class "Default")
      (node (ref "D53") (pin "+") (pinfunction "+_+") (pintype "passive"))
      (node (ref "R68") (pin "2") (pinfunction "2_2") (pintype "passive"))
    )
    (net (code "74") (name "Net-(D54-Pad+)") (class "Default")
      (node (ref "D54") (pin "+") (pinfunction "+_+") (pintype "passive"))
      (node (ref "R69") (pin "2") (pinfunction "2_2") (pintype "passive"))
    )
    (net (code "75") (name "Net-(D55-Pad+)") (class "Default")
      (node (ref "D55") (pin "+") (pinfunction "+_+") (pintype "passive"))
      (node (ref "R70") (pin "2") (pinfunction "2_2") (pintype "passive"))
    )
    (net (code "76") (name "Net-(D56-Pad+)") (class "Default")
      (node (ref "D56") (pin "+") (pinfunction "+_+") (pintype "passive"))
      (node (ref "R72") (pin "2") (pinfunction "2_2") (pintype "passive"))
    )
    (net (code "77") (name "Net-(D57-Pad+)") (class "Default")
      (node (ref "D57") (pin "+") (pinfunction "+_+") (pintype "passive"))
      (node (ref "R73") (pin "2") (pinfunction "2_2") (pintype "passive"))
    )
    (net (code "78") (name "Net-(D58-Pad+)") (class "Default")
      (node (ref "D58") (pin "+") (pinfunction "+_+") (pintype "passive"))
      (node (ref "R74") (pin "2") (pinfunction "2_2") (pintype "passive"))
    )
    (net (code "79") (name "Net-(D59-Pad+)") (class "Default")
      (node (ref "D59") (pin "+") (pinfunction "+_+") (pintype "passive"))
      (node (ref "R75") (pin "2") (pinfunction "2_2") (pintype "passive"))
    )
    (net (code "80") (name "Net-(D60-Pad+)") (class "Default")
      (node (ref "D60") (pin "+") (pinfunction "+_+") (pintype "passive"))
      (node (ref "R76") (pin "2") (pinfunction "2_2") (pintype "passive"))
    )
    (net (code "81") (name "Net-(D61-Pad+)") (class "Default")
      (node (ref "D61") (pin "+") (pinfunction "+_+") (pintype "passive"))
      (node (ref "R77") (pin "2") (pinfunction "2_2") (pintype "passive"))
    )
    (net (code "82") (name "Net-(D62-Pad+)") (class "Default")
      (node (ref "D62") (pin "+") (pinfunction "+_+") (pintype "passive"))
      (node (ref "R79") (pin "2") (pinfunction "2_2") (pintype "passive"))
    )
    (net (code "83") (name "Net-(D63-Pad+)") (class "Default")
      (node (ref "D63") (pin "+") (pinfunction "+_+") (pintype "passive"))
      (node (ref "R80") (pin "2") (pinfunction "2_2") (pintype "passive"))
    )
    (net (code "84") (name "Net-(D64-Pad+)") (class "Default")
      (node (ref "D64") (pin "+") (pinfunction "+_+") (pintype "passive"))
      (node (ref "R81") (pin "2") (pinfunction "2_2") (pintype "passive"))
    )
    (net (code "85") (name "Net-(D65-Pad+)") (class "Default")
      (node (ref "D65") (pin "+") (pinfunction "+_+") (pintype "passive"))
      (node (ref "R82") (pin "2") (pinfunction "2_2") (pintype "passive"))
    )
    (net (code "86") (name "Net-(D66-Pad+)") (class "Default")
      (node (ref "D66") (pin "+") (pinfunction "+_+") (pintype "passive"))
      (node (ref "R83") (pin "2") (pinfunction "2_2") (pintype "passive"))
    )
    (net (code "87") (name "Net-(D67-Pad+)") (class "Default")
      (node (ref "D67") (pin "+") (pinfunction "+_+") (pintype "passive"))
      (node (ref "R84") (pin "2") (pinfunction "2_2") (pintype "passive"))
    )
    (net (code "88") (name "Net-(D68-Pad+)") (class "Default")
      (node (ref "D68") (pin "+") (pinfunction "+_+") (pintype "passive"))
      (node (ref "R86") (pin "2") (pinfunction "2_2") (pintype "passive"))
    )
    (net (code "89") (name "Net-(D69-Pad+)") (class "Default")
      (node (ref "D69") (pin "+") (pinfunction "+_+") (pintype "passive"))
      (node (ref "R87") (pin "2") (pinfunction "2_2") (pintype "passive"))
    )
    (net (code "90") (name "Net-(D70-Pad+)") (class "Default")
      (node (ref "D70") (pin "+") (pinfunction "+_+") (pintype "passive"))
      (node (ref "R88") (pin "2") (pinfunction "2_2") (pintype "passive"))
    )
    (net (code "91") (name "Net-(D71-Pad+)") (class "Default")
      (node (ref "D71") (pin "+") (pinfunction "+_+") (pintype "passive"))
      (node (ref "R89") (pin "2") (pinfunction "2_2") (pintype "passive"))
    )
    (net (code "92") (name "Net-(D72-Pad+)") (class "Default")
      (node (ref "D72") (pin "+") (pinfunction "+_+") (pintype "passive"))
      (node (ref "R90") (pin "2") (pinfunction "2_2") (pintype "passive"))
    )
    (net (code "93") (name "Net-(D73-Pad+)") (class "Default")
      (node (ref "D73") (pin "+") (pinfunction "+_+") (pintype "passive"))
      (node (ref "R91") (pin "2") (pinfunction "2_2") (pintype "passive"))
    )
    (net (code "94") (name "Net-(D74-Pad+)") (class "Default")
      (node (ref "D74") (pin "+") (pinfunction "+_+") (pintype "passive"))
      (node (ref "R93") (pin "2") (pinfunction "2_2") (pintype "passive"))
    )
    (net (code "95") (name "Net-(D75-Pad+)") (class "Default")
      (node (ref "D75") (pin "+") (pinfunction "+_+") (pintype "passive"))
      (node (ref "R94") (pin "2") (pinfunction "2_2") (pintype "passive"))
    )
    (net (code "96") (name "Net-(D76-Pad+)") (class "Default")
      (node (ref "D76") (pin "+") (pinfunction "+_+") (pintype "passive"))
      (node (ref "R95") (pin "2") (pinfunction "2_2") (pintype "passive"))
    )
    (net (code "97") (name "Net-(D77-Pad+)") (class "Default")
      (node (ref "D77") (pin "+") (pinfunction "+_+") (pintype "passive"))
      (node (ref "R96") (pin "2") (pinfunction "2_2") (pintype "passive"))
    )
    (net (code "98") (name "Net-(D78-Pad+)") (class "Default")
      (node (ref "D78") (pin "+") (pinfunction "+_+") (pintype "passive"))
      (node (ref "R97") (pin "2") (pinfunction "2_2") (pintype "passive"))
    )
    (net (code "99") (name "Net-(D79-Pad+)") (class "Default")
      (node (ref "D79") (pin "+") (pinfunction "+_+") (pintype "passive"))
      (node (ref "R98") (pin "2") (pinfunction "2_2") (pintype "passive"))
    )
    (net (code "100") (name "Net-(J2-Pad3)") (class "Default")
      (node (ref "J2") (pin "3") (pinfunction "3_3") (pintype "passive"))
      (node (ref "J3") (pin "3") (pinfunction "3_3") (pintype "passive"))
      (node (ref "J4") (pin "3") (pinfunction "3_3") (pintype "passive"))
      (node (ref "R2") (pin "1") (pinfunction "1_1") (pintype "passive"))
      (node (ref "R3") (pin "2") (pinfunction "2_2") (pintype "passive"))
    )
    (net (code "101") (name "Net-(Q1-D)") (class "Default")
      (node (ref "D2") (pin "-") (pinfunction "-_-") (pintype "passive"))
      (node (ref "D3") (pin "-") (pinfunction "-_-") (pintype "passive"))
      (node (ref "D4") (pin "-") (pinfunction "-_-") (pintype "passive"))
      (node (ref "D5") (pin "-") (pinfunction "-_-") (pintype "passive"))
      (node (ref "D6") (pin "-") (pinfunction "-_-") (pintype "passive"))
      (node (ref "D7") (pin "-") (pinfunction "-_-") (pintype "passive"))
      (node (ref "Q1") (pin "3") (pinfunction "D_3") (pintype "passive"))
    )
    (net (code "102") (name "Net-(Q2-D)") (class "Default")
      (node (ref "D13") (pin "-") (pinfunction "-_-") (pintype "passive"))
      (node (ref "D14") (pin "-") (pinfunction "-_-") (pintype "passive"))
      (node (ref "D15") (pin "-") (pinfunction "-_-") (pintype "passive"))
      (node (ref "D16") (pin "-") (pinfunction "-_-") (pintype "passive"))
      (node (ref "D17") (pin "-") (pinfunction "-_-") (pintype "passive"))
      (node (ref "D18") (pin "-") (pinfunction "-_-") (pintype "passive"))
      (node (ref "Q2") (pin "3") (pinfunction "D_3") (pintype "passive"))
    )
    (net (code "103") (name "Net-(Q3-D)") (class "Default")
      (node (ref "D10") (pin "-") (pinfunction "-_-") (pintype "passive"))
      (node (ref "D11") (pin "-") (pinfunction "-_-") (pintype "passive"))
      (node (ref "D12") (pin "-") (pinfunction "-_-") (pintype "passive"))
      (node (ref "D19") (pin "-") (pinfunction "-_-") (pintype "passive"))
      (node (ref "D8") (pin "-") (pinfunction "-_-") (pintype "passive"))
      (node (ref "D9") (pin "-") (pinfunction "-_-") (pintype "passive"))
      (node (ref "Q3") (pin "3") (pinfunction "D_3") (pintype "passive"))
    )
    (net (code "104") (name "Net-(Q4-D)") (class "Default")
      (node (ref "D20") (pin "-") (pinfunction "-_-") (pintype "passive"))
      (node (ref "D21") (pin "-") (pinfunction "-_-") (pintype "passive"))
      (node (ref "D22") (pin "-") (pinfunction "-_-") (pintype "passive"))
      (node (ref "D23") (pin "-") (pinfunction "-_-") (pintype "passive"))
      (node (ref "D24") (pin "-") (pinfunction "-_-") (pintype "passive"))
      (node (ref "D25") (pin "-") (pinfunction "-_-") (pintype "passive"))
      (node (ref "Q4") (pin "3") (pinfunction "D_3") (pintype "passive"))
    )
    (net (code "105") (name "Net-(Q5-D)") (class "Default")
      (node (ref "D26") (pin "-") (pinfunction "-_-") (pintype "passive"))
      (node (ref "D27") (pin "-") (pinfunction "-_-") (pintype "passive"))
      (node (ref "D28") (pin "-") (pinfunction "-_-") (pintype "passive"))
      (node (ref "D29") (pin "-") (pinfunction "-_-") (pintype "passive"))
      (node (ref "D30") (pin "-") (pinfunction "-_-") (pintype "passive"))
      (node (ref "D31") (pin "-") (pinfunction "-_-") (pintype "passive"))
      (node (ref "Q5") (pin "3") (pinfunction "D_3") (pintype "passive"))
    )
    (net (code "106") (name "Net-(Q6-D)") (class "Default")
      (node (ref "D32") (pin "-") (pinfunction "-_-") (pintype "passive"))
      (node (ref "D33") (pin "-") (pinfunction "-_-") (pintype "passive"))
      (node (ref "D34") (pin "-") (pinfunction "-_-") (pintype "passive"))
      (node (ref "D35") (pin "-") (pinfunction "-_-") (pintype "passive"))
      (node (ref "D36") (pin "-") (pinfunction "-_-") (pintype "passive"))
      (node (ref "D37") (pin "-") (pinfunction "-_-") (pintype "passive"))
      (node (ref "Q6") (pin "3") (pinfunction "D_3") (pintype "passive"))
    )
    (net (code "107") (name "Net-(Q7-D)") (class "Default")
      (node (ref "D38") (pin "-") (pinfunction "-_-") (pintype "passive"))
      (node (ref "D39") (pin "-") (pinfunction "-_-") (pintype "passive"))
      (node (ref "D40") (pin "-") (pinfunction "-_-") (pintype "passive"))
      (node (ref "D41") (pin "-") (pinfunction "-_-") (pintype "passive"))
      (node (ref "D42") (pin "-") (pinfunction "-_-") (pintype "passive"))
      (node (ref "D43") (pin "-") (pinfunction "-_-") (pintype "passive"))
      (node (ref "Q7") (pin "3") (pinfunction "D_3") (pintype "passive"))
    )
    (net (code "108") (name "Net-(Q8-D)") (class "Default")
      (node (ref "D44") (pin "-") (pinfunction "-_-") (pintype "passive"))
      (node (ref "D45") (pin "-") (pinfunction "-_-") (pintype "passive"))
      (node (ref "D46") (pin "-") (pinfunction "-_-") (pintype "passive"))
      (node (ref "D47") (pin "-") (pinfunction "-_-") (pintype "passive"))
      (node (ref "D48") (pin "-") (pinfunction "-_-") (pintype "passive"))
      (node (ref "D49") (pin "-") (pinfunction "-_-") (pintype "passive"))
      (node (ref "Q8") (pin "3") (pinfunction "D_3") (pintype "passive"))
    )
    (net (code "109") (name "Net-(Q9-D)") (class "Default")
      (node (ref "D50") (pin "-") (pinfunction "-_-") (pintype "passive"))
      (node (ref "D51") (pin "-") (pinfunction "-_-") (pintype "passive"))
      (node (ref "D52") (pin "-") (pinfunction "-_-") (pintype "passive"))
      (node (ref "D53") (pin "-") (pinfunction "-_-") (pintype "passive"))
      (node (ref "D54") (pin "-") (pinfunction "-_-") (pintype "passive"))
      (node (ref "D55") (pin "-") (pinfunction "-_-") (pintype "passive"))
      (node (ref "Q9") (pin "3") (pinfunction "D_3") (pintype "passive"))
    )
    (net (code "110") (name "Net-(Q10-D)") (class "Default")
      (node (ref "D56") (pin "-") (pinfunction "-_-") (pintype "passive"))
      (node (ref "D57") (pin "-") (pinfunction "-_-") (pintype "passive"))
      (node (ref "D58") (pin "-") (pinfunction "-_-") (pintype "passive"))
      (node (ref "D59") (pin "-") (pinfunction "-_-") (pintype "passive"))
      (node (ref "D60") (pin "-") (pinfunction "-_-") (pintype "passive"))
      (node (ref "D61") (pin "-") (pinfunction "-_-") (pintype "passive"))
      (node (ref "Q10") (pin "3") (pinfunction "D_3") (pintype "passive"))
    )
    (net (code "111") (name "Net-(Q11-D)") (class "Default")
      (node (ref "D62") (pin "-") (pinfunction "-_-") (pintype "passive"))
      (node (ref "D63") (pin "-") (pinfunction "-_-") (pintype "passive"))
      (node (ref "D64") (pin "-") (pinfunction "-_-") (pintype "passive"))
      (node (ref "D65") (pin "-") (pinfunction "-_-") (pintype "passive"))
      (node (ref "D66") (pin "-") (pinfunction "-_-") (pintype "passive"))
      (node (ref "D67") (pin "-") (pinfunction "-_-") (pintype "passive"))
      (node (ref "Q11") (pin "3") (pinfunction "D_3") (pintype "passive"))
    )
    (net (code "112") (name "Net-(Q12-D)") (class "Default")
      (node (ref "D68") (pin "-") (pinfunction "-_-") (pintype "passive"))
      (node (ref "D69") (pin "-") (pinfunction "-_-") (pintype "passive"))
      (node (ref "D70") (pin "-") (pinfunction "-_-") (pintype "passive"))
      (node (ref "D71") (pin "-") (pinfunction "-_-") (pintype "passive"))
      (node (ref "D72") (pin "-") (pinfunction "-_-") (pintype "passive"))
      (node (ref "D73") (pin "-") (pinfunction "-_-") (pintype "passive"))
      (node (ref "Q12") (pin "3") (pinfunction "D_3") (pintype "passive"))
    )
    (net (code "113") (name "Net-(Q13-D)") (class "Default")
      (node (ref "D74") (pin "-") (pinfunction "-_-") (pintype "passive"))
      (node (ref "D75") (pin "-") (pinfunction "-_-") (pintype "passive"))
      (node (ref "D76") (pin "-") (pinfunction "-_-") (pintype "passive"))
      (node (ref "D77") (pin "-") (pinfunction "-_-") (pintype "passive"))
      (node (ref "D78") (pin "-") (pinfunction "-_-") (pintype "passive"))
      (node (ref "D79") (pin "-") (pinfunction "-_-") (pintype "passive"))
      (node (ref "Q13") (pin "3") (pinfunction "D_3") (pintype "passive"))
    )
    (net (code "114") (name "Net-(R8-Pad2)") (class "Default")
      (node (ref "R8") (pin "2") (pinfunction "2_2") (pintype "passive"))
      (node (ref "TX") (pin "+") (pinfunction "+_+") (pintype "passive"))
    )
    (net (code "115") (name "Net-(R9-Pad2)") (class "Default")
      (node (ref "R9") (pin "2") (pinfunction "2_2") (pintype "passive"))
      (node (ref "RX") (pin "+") (pinfunction "+_+") (pintype "passive"))
    )
    (net (code "116") (name "Net-(U2-AREF)") (class "Default")
      (node (ref "R7") (pin "1") (pinfunction "1_1") (pintype "passive"))
      (node (ref "U2") (pin "20") (pinfunction "AREF_20") (pintype "bidirectional"))
    )
    (net (code "117") (name "Net-(U2-PB6(XTAL1{slash}TOSC1))") (class "Default")
      (node (ref "C4") (pin "2") (pinfunction "2_2") (pintype "passive"))
      (node (ref "U2") (pin "7") (pinfunction "PB6(XTAL1/TOSC1)_7") (pintype "bidirectional"))
      (node (ref "Y1") (pin "2") (pinfunction "2_2") (pintype "passive"))
    )
    (net (code "118") (name "Net-(U2-PB7(XTAL2{slash}TOSC2))") (class "Default")
      (node (ref "C2") (pin "2") (pinfunction "2_2") (pintype "passive"))
      (node (ref "U2") (pin "8") (pinfunction "PB7(XTAL2/TOSC2)_8") (pintype "bidirectional"))
      (node (ref "Y1") (pin "1") (pinfunction "1_1") (pintype "passive"))
    )
    (net (code "119") (name "Net-(U2-PC0(ADC0))") (class "Default")
      (node (ref "R1") (pin "2") (pinfunction "2_2") (pintype "passive"))
      (node (ref "U2") (pin "23") (pinfunction "PC0(ADC0)_23") (pintype "bidirectional"))
    )
    (net (code "120") (name "Net-(U2-PC1(ADC1))") (class "Default")
      (node (ref "R5") (pin "2") (pinfunction "2_2") (pintype "passive"))
      (node (ref "U2") (pin "24") (pinfunction "PC1(ADC1)_24") (pintype "bidirectional"))
    )
    (net (code "121") (name "Net-(U2-PC6({slash}RESET))") (class "Default")
      (node (ref "C5") (pin "1") (pinfunction "1_1") (pintype "passive"))
      (node (ref "ICSP") (pin "5") (pinfunction "5_5") (pintype "passive"))
      (node (ref "R") (pin "1") (pinfunction "1_1") (pintype "passive"))
      (node (ref "SW1") (pin "1") (pinfunction "1_1") (pintype "bidirectional"))
      (node (ref "U2") (pin "29") (pinfunction "PC6(/RESET)_29") (pintype "bidirectional"))
    )
    (net (code "122") (name "Net-(U2-PD1(TXD))") (class "Default")
      (node (ref "R6") (pin "2") (pinfunction "2_2") (pintype "passive"))
      (node (ref "U2") (pin "31") (pinfunction "PD1(TXD)_31") (pintype "bidirectional"))
    )
    (net (code "123") (name "PULSEIN") (class "Default")
      (node (ref "R1") (pin "1") (pinfunction "1_1") (pintype "passive"))
      (node (ref "RJ45") (pin "1-4") (pinfunction "4_1-4") (pintype "passive"))
    )
    (net (code "124") (name "PULSEOUT") (class "Default")
      (node (ref "R5") (pin "1") (pinfunction "1_1") (pintype "passive"))
      (node (ref "RJ45") (pin "2-4") (pinfunction "4_2-4") (pintype "passive"))
    )
    (net (code "125") (name "RX") (class "Default")
      (node (ref "R100") (pin "2") (pinfunction "2_2") (pintype "passive"))
      (node (ref "RJ45") (pin "1-3") (pinfunction "3_1-3") (pintype "passive"))
      (node (ref "U2") (pin "30") (pinfunction "PD0(RXD)_30") (pintype "bidirectional"))
      (node (ref "USB-TTL") (pin "3") (pinfunction "3_3") (pintype "passive"))
    )
    (net (code "126") (name "RXLED") (class "Default")
      (node (ref "R9") (pin "1") (pinfunction "1_1") (pintype "passive"))
      (node (ref "U2") (pin "32") (pinfunction "PD2(INT0)_32") (pintype "bidirectional"))
    )
    (net (code "127") (name "SHUTTER") (class "Default")
      (node (ref "R2") (pin "2") (pinfunction "2_2") (pintype "passive"))
      (node (ref "U2") (pin "25") (pinfunction "PC2(ADC2)_25") (pintype "bidirectional"))
    )
    (net (code "128") (name "TX") (class "Default")
      (node (ref "R6") (pin "1") (pinfunction "1_1") (pintype "passive"))
      (node (ref "RJ45") (pin "2-3") (pinfunction "3_2-3") (pintype "passive"))
      (node (ref "USB-TTL") (pin "2") (pinfunction "2_2") (pintype "passive"))
    )
    (net (code "129") (name "TXLED") (class "Default")
      (node (ref "R8") (pin "1") (pinfunction "1_1") (pintype "passive"))
      (node (ref "U2") (pin "1") (pinfunction "PD3(INT1)_1") (pintype "bidirectional"))
    )
    (net (code "130") (name "unconnected-(J2-Pad2)") (class "Default")
      (node (ref "J2") (pin "2") (pinfunction "2_2") (pintype "passive"))
    )
    (net (code "131") (name "unconnected-(J3-Pad2)") (class "Default")
      (node (ref "J3") (pin "2") (pinfunction "2_2") (pintype "passive"))
    )
    (net (code "132") (name "unconnected-(J4-Pad2)") (class "Default")
      (node (ref "J4") (pin "2") (pinfunction "2_2") (pintype "passive"))
    )
    (net (code "133") (name "unconnected-(J5-Pad1)") (class "Default")
      (node (ref "J5") (pin "1") (pinfunction "1_1") (pintype "bidirectional"))
    )
    (net (code "134") (name "unconnected-(J5-Pad3)") (class "Default")
      (node (ref "J5") (pin "3") (pinfunction "3_3") (pintype "bidirectional"))
    )
  )
)
